# oresat-backplane-1u.net
KiCad netlist of a schematic drawn in EAGLE
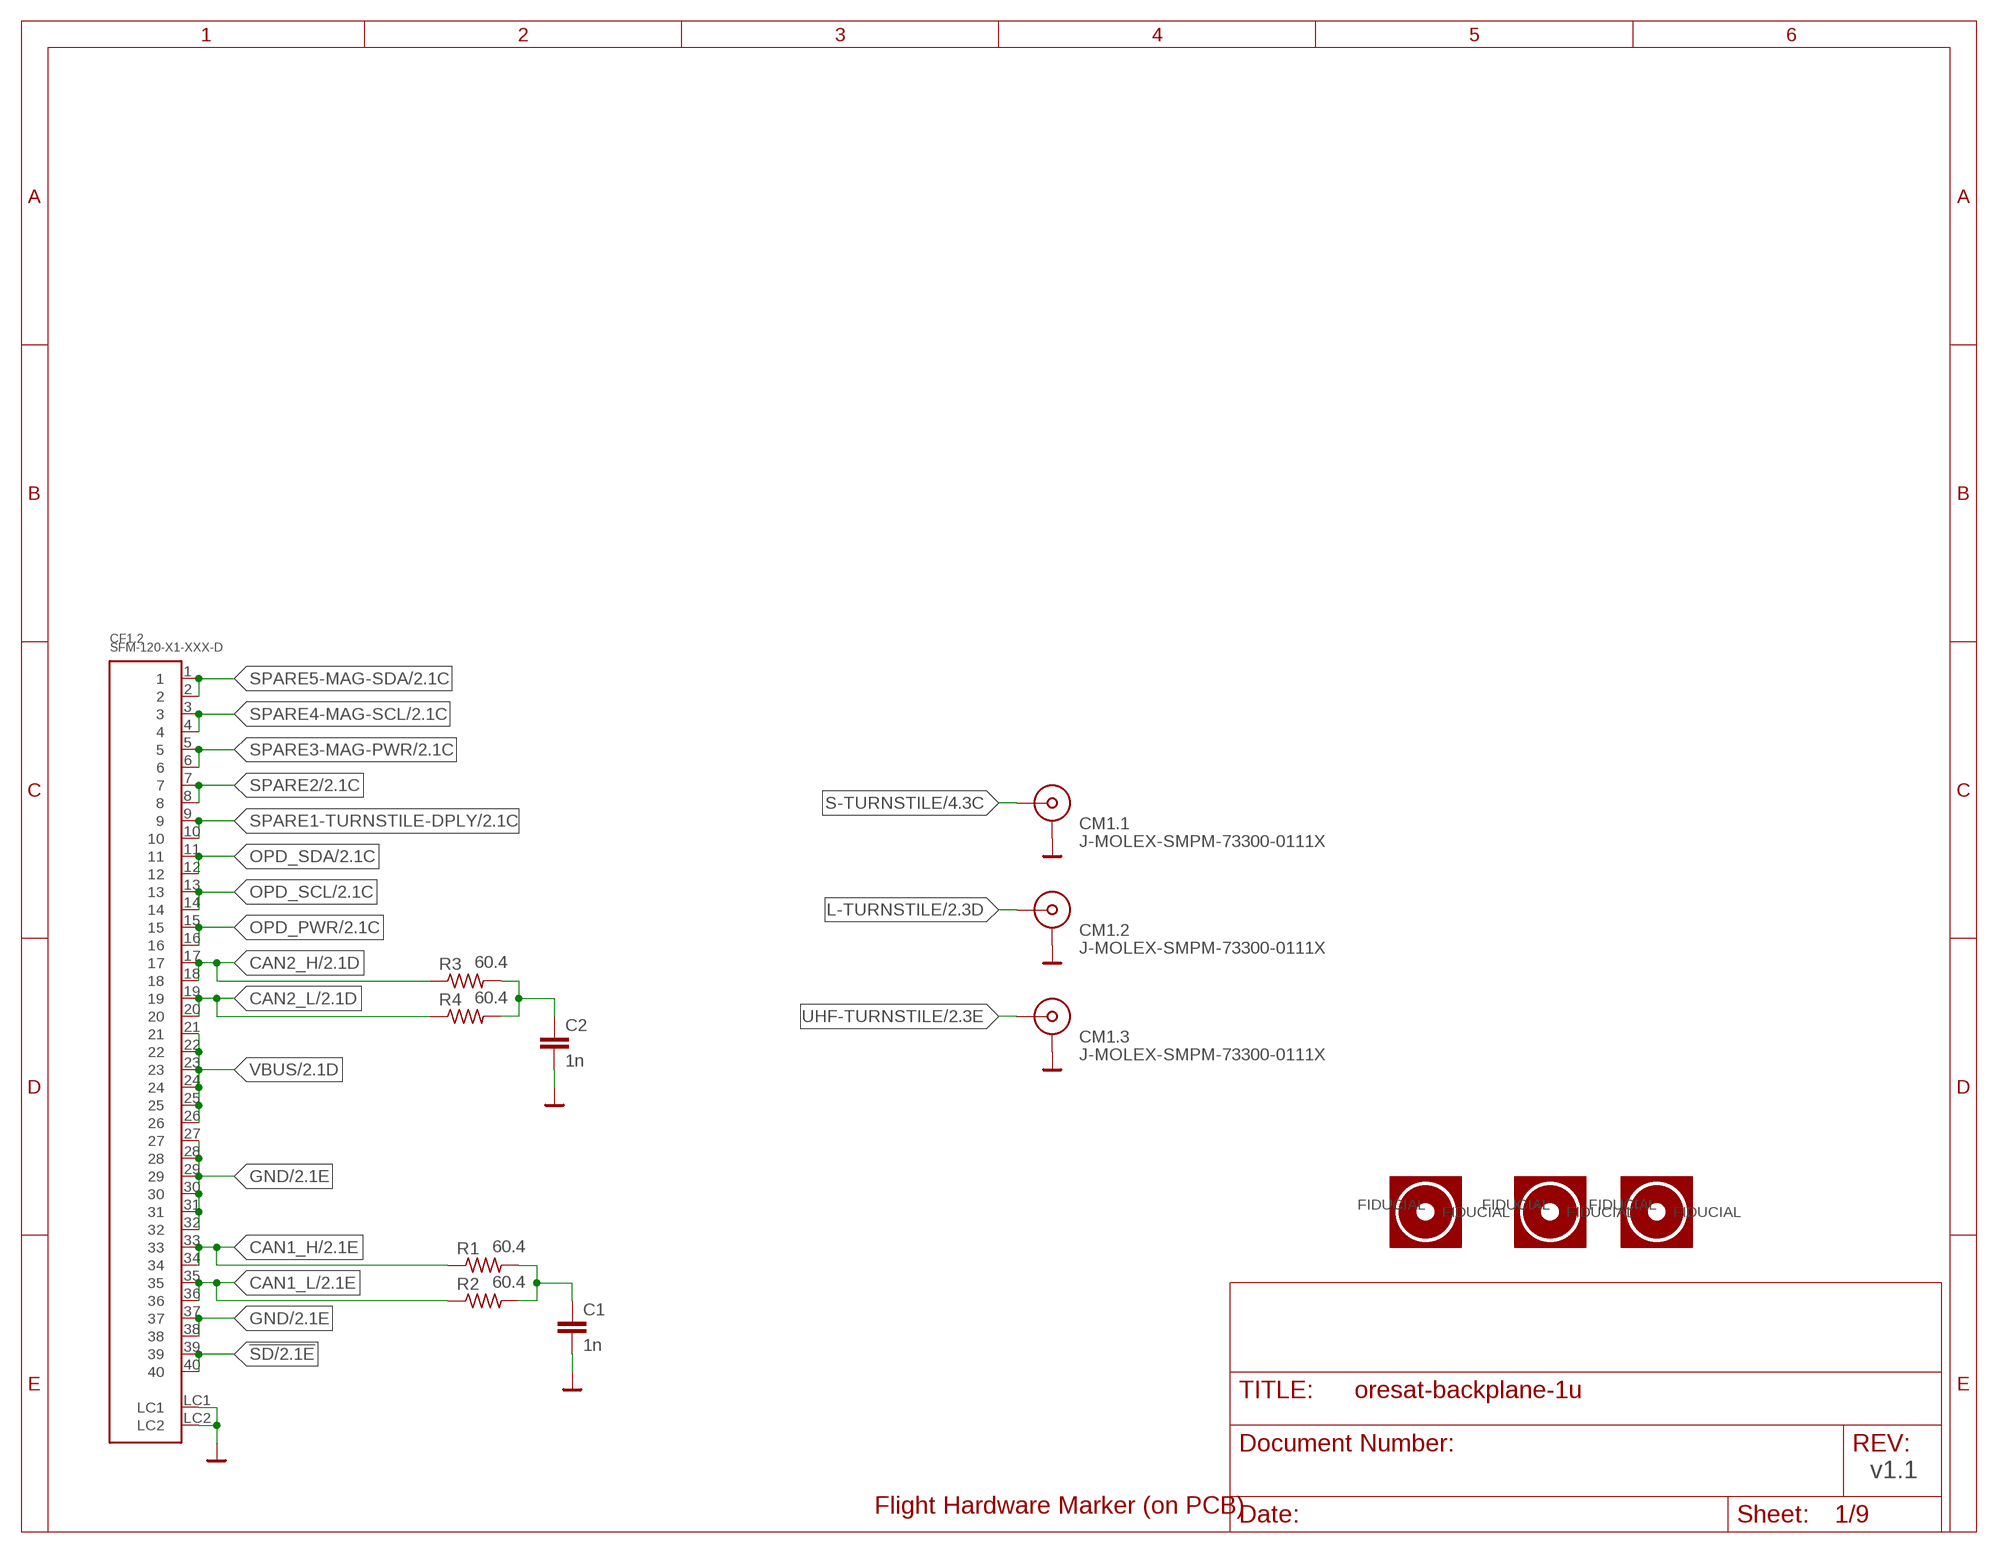
[diagram p0: schematic, sheet 1]
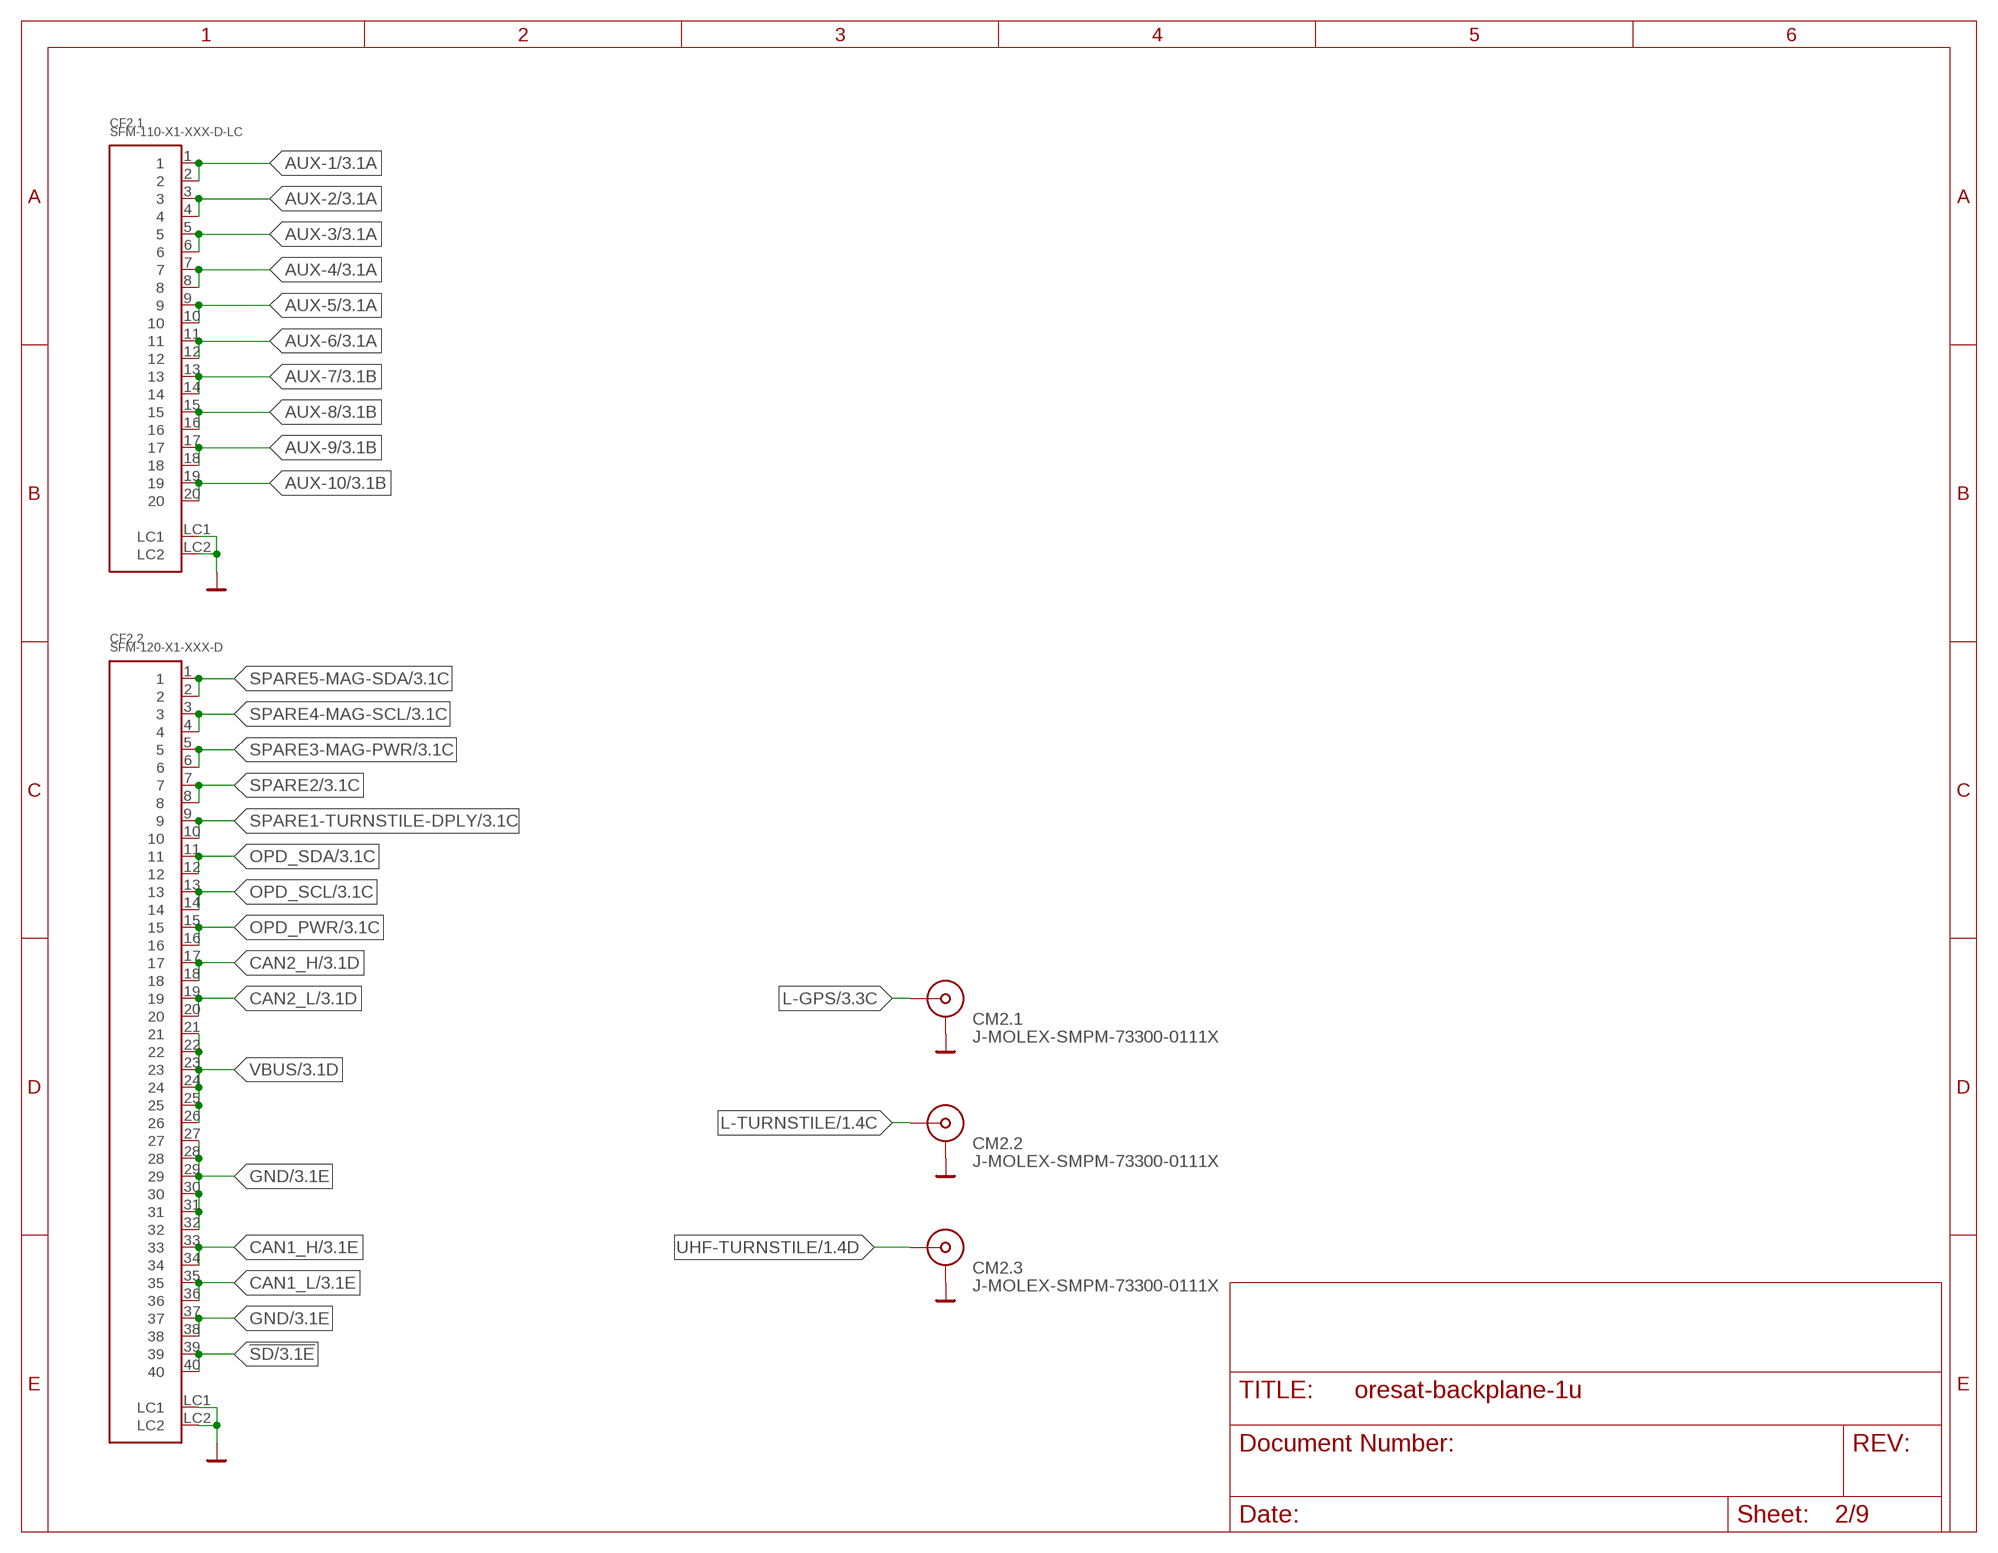
[diagram p1: schematic, sheet 2]
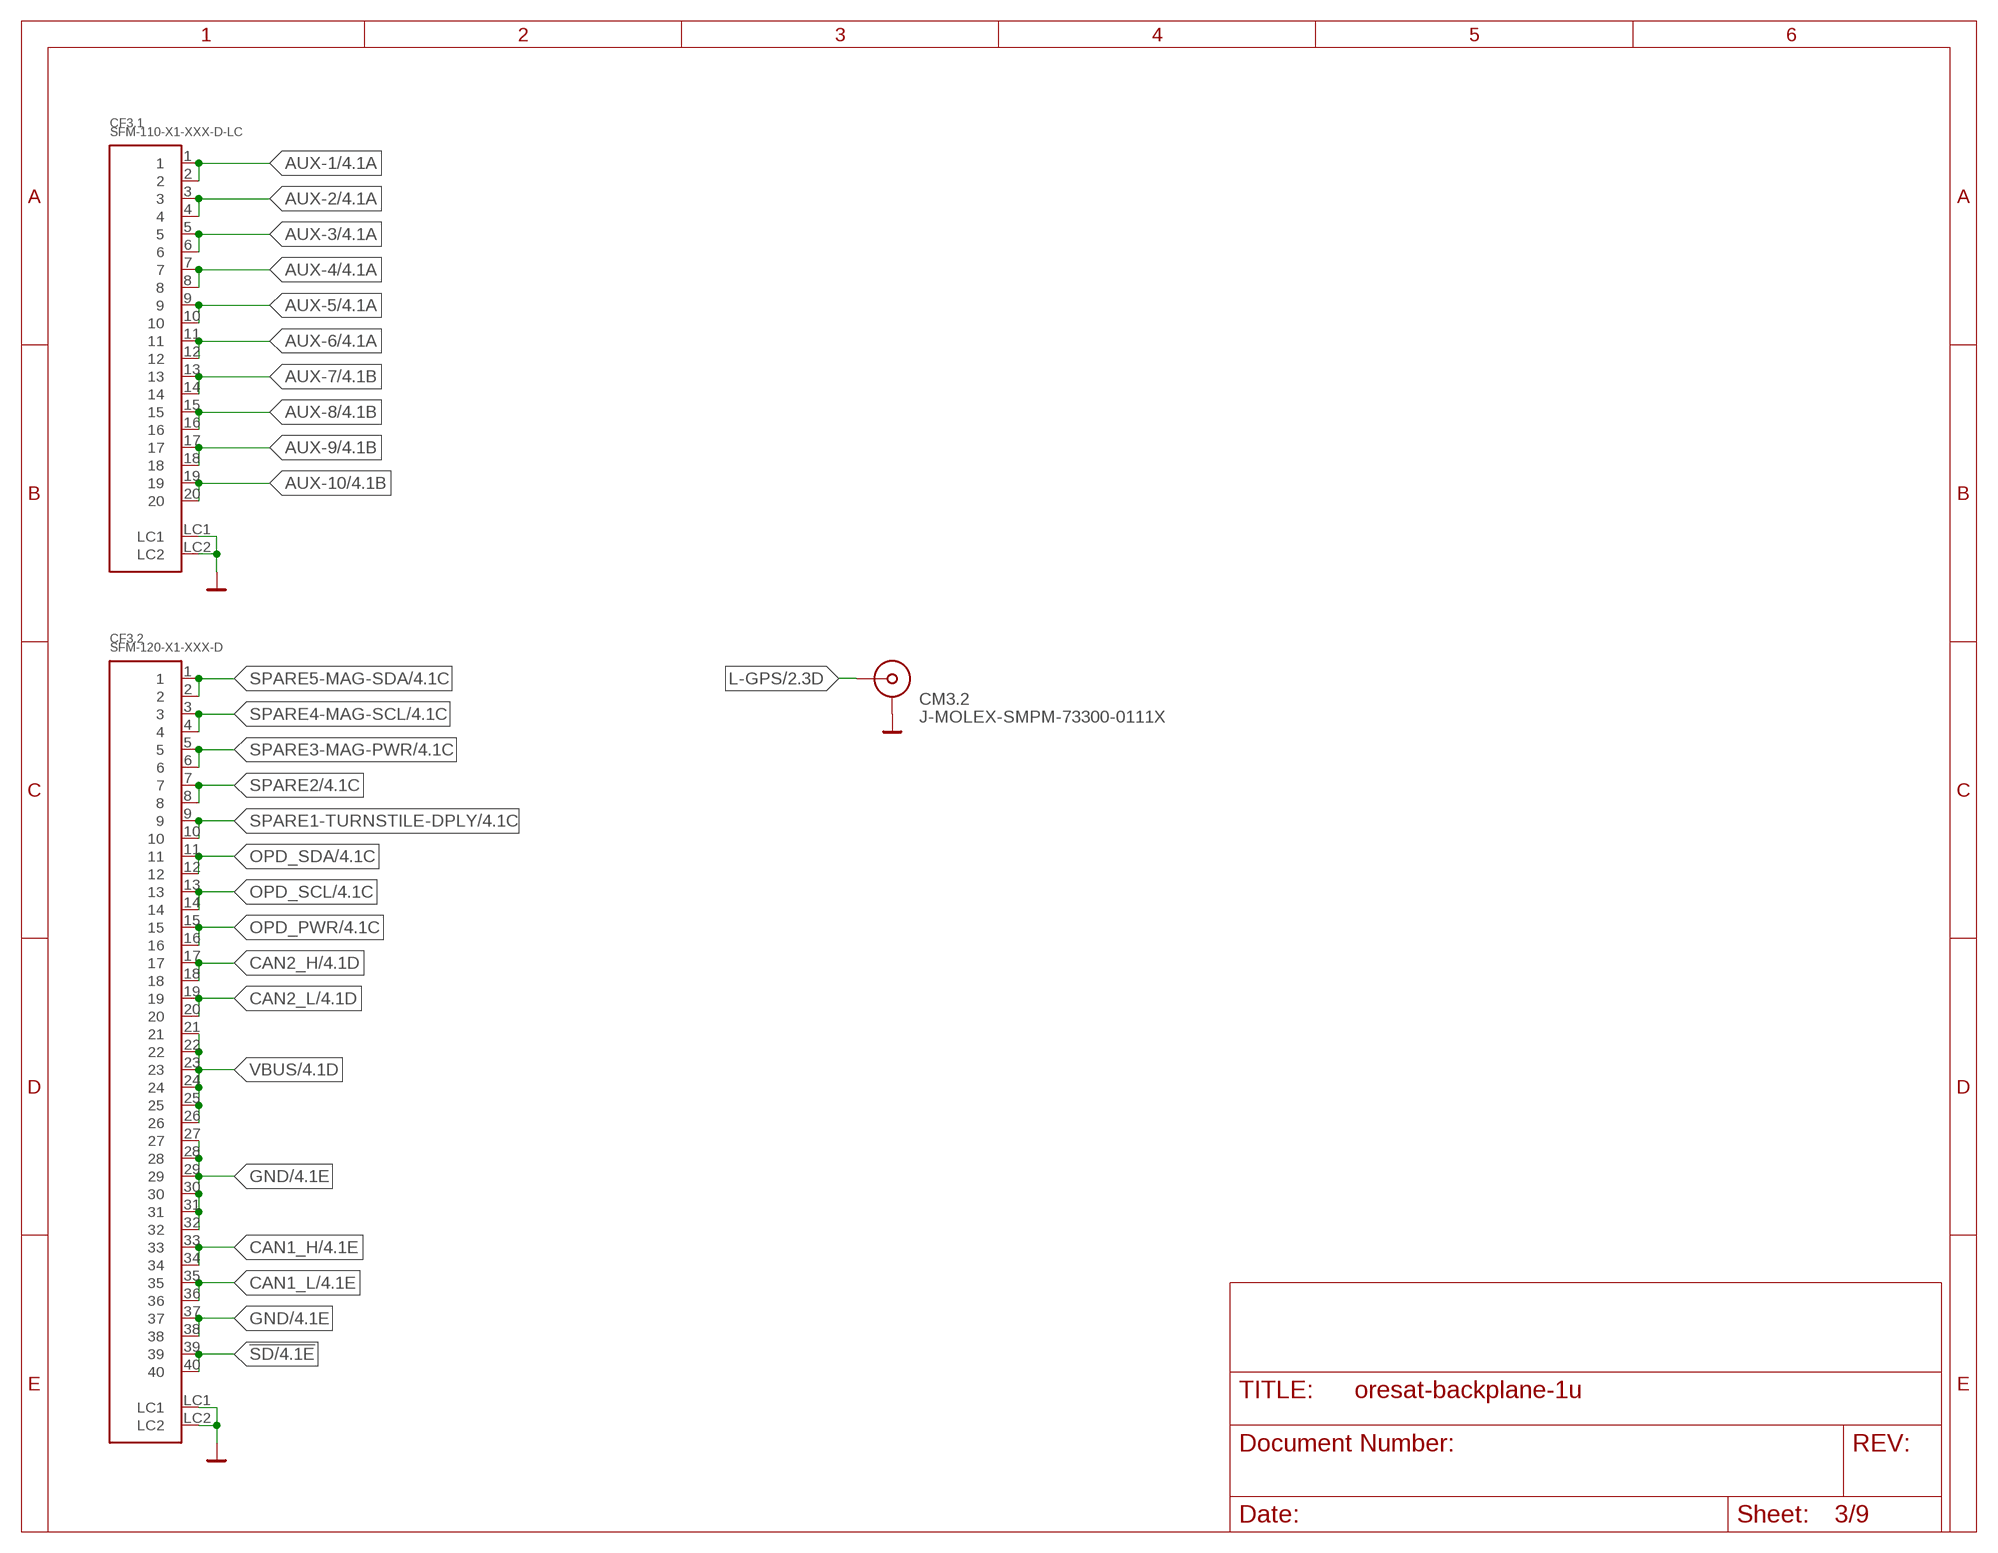
[diagram p2: schematic, sheet 3]
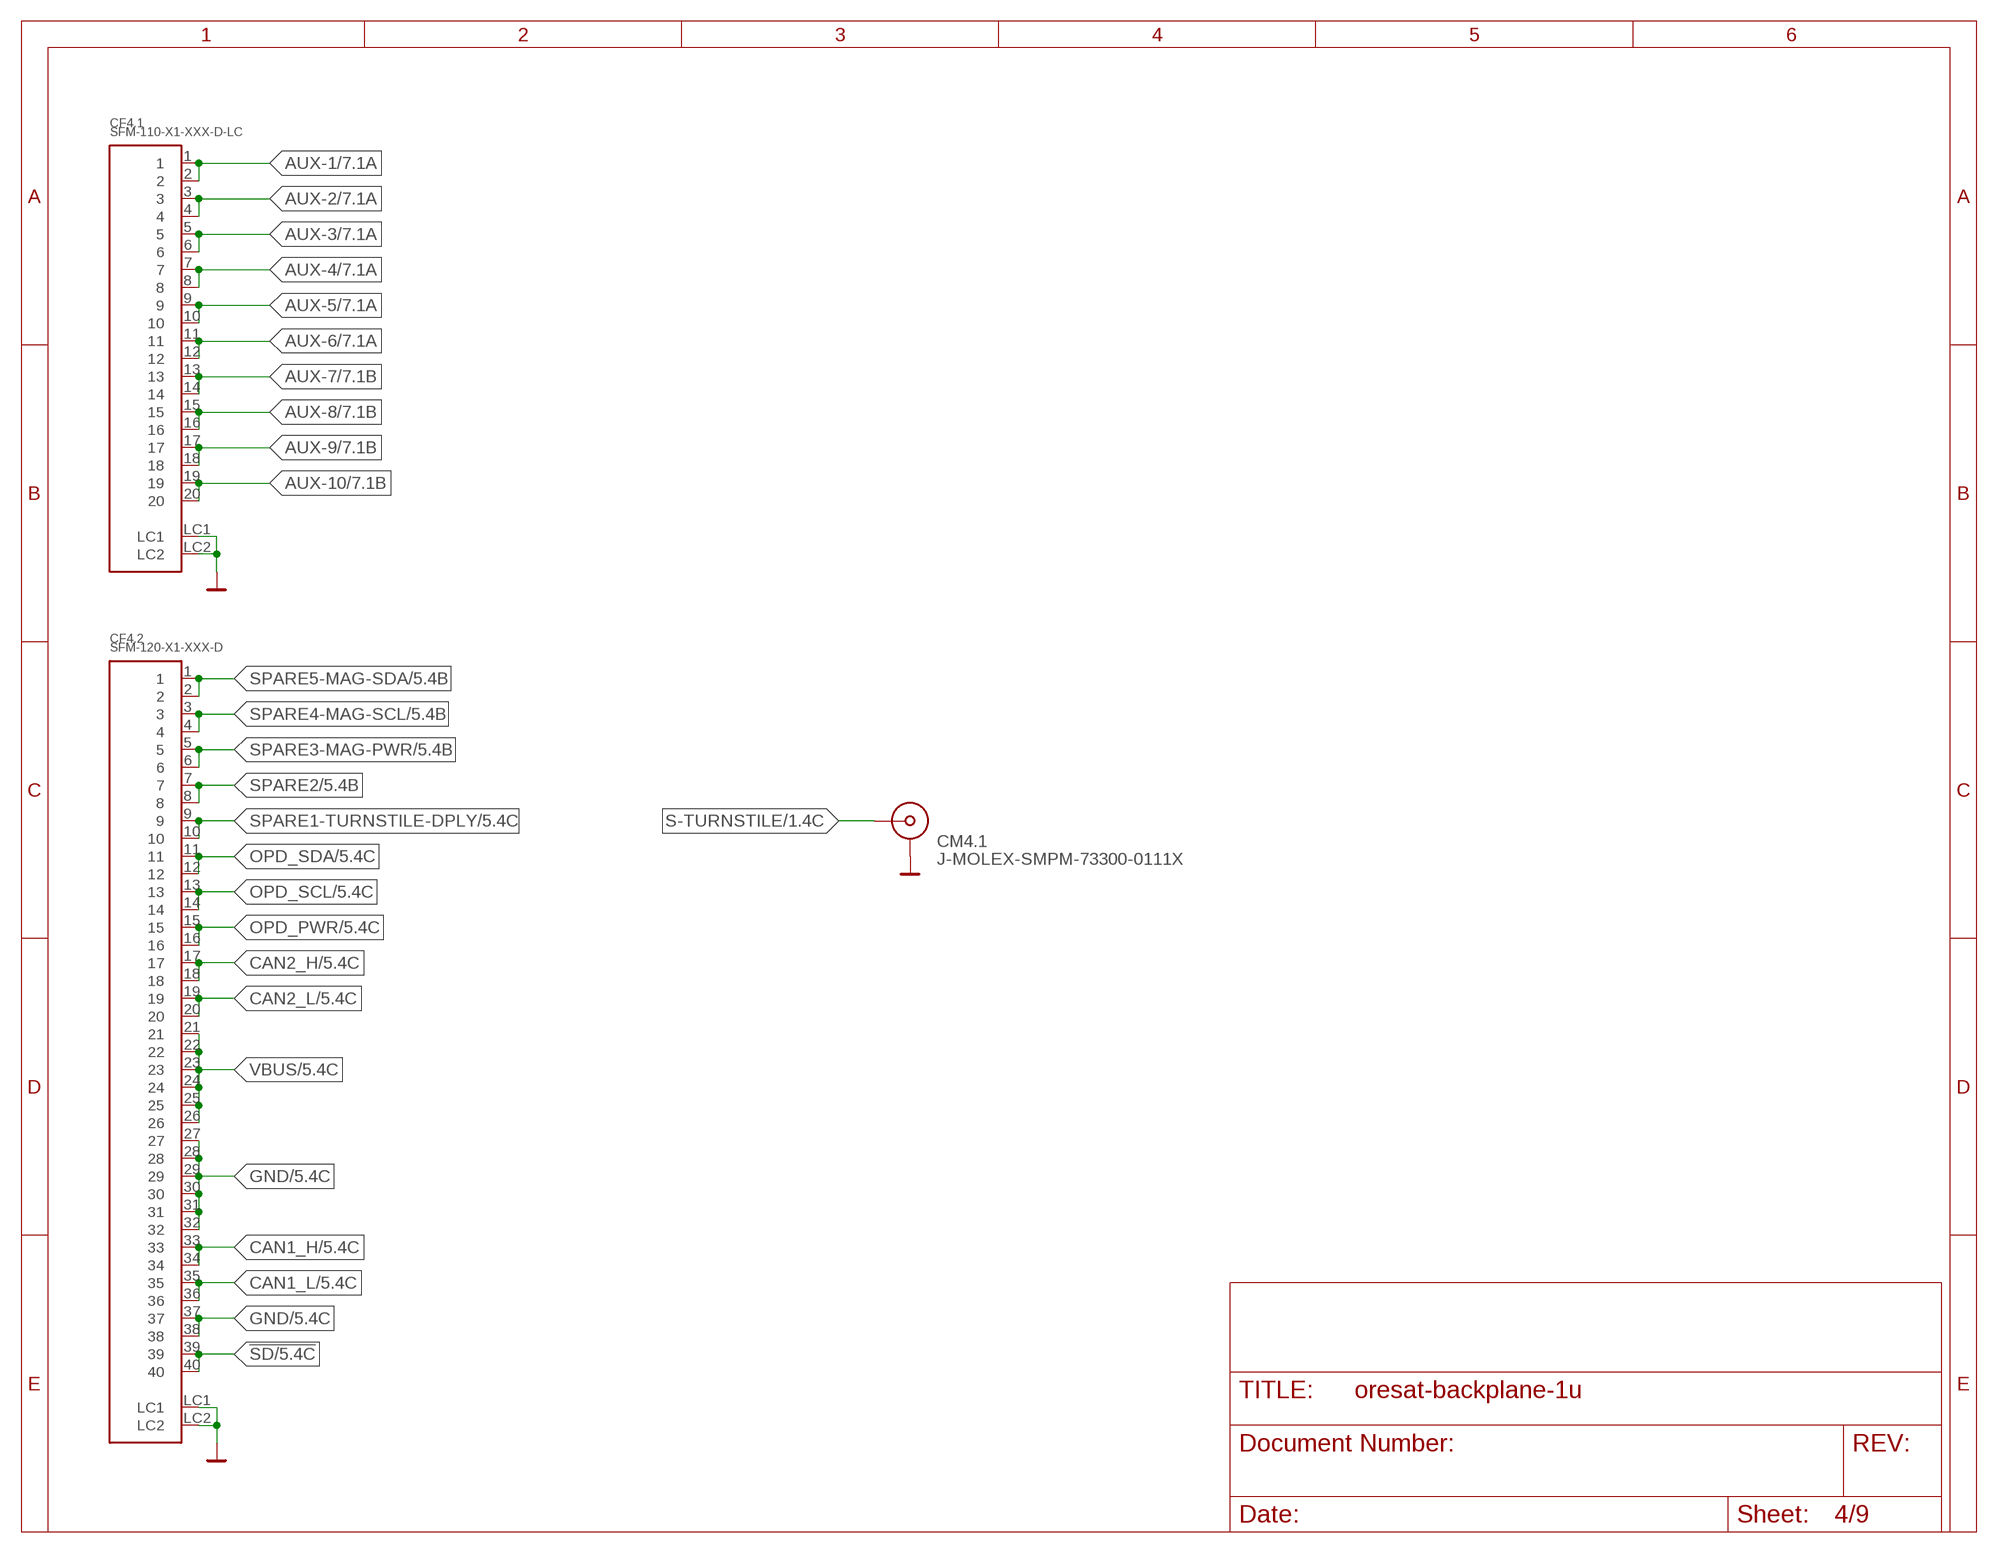
[diagram p3: schematic, sheet 4]
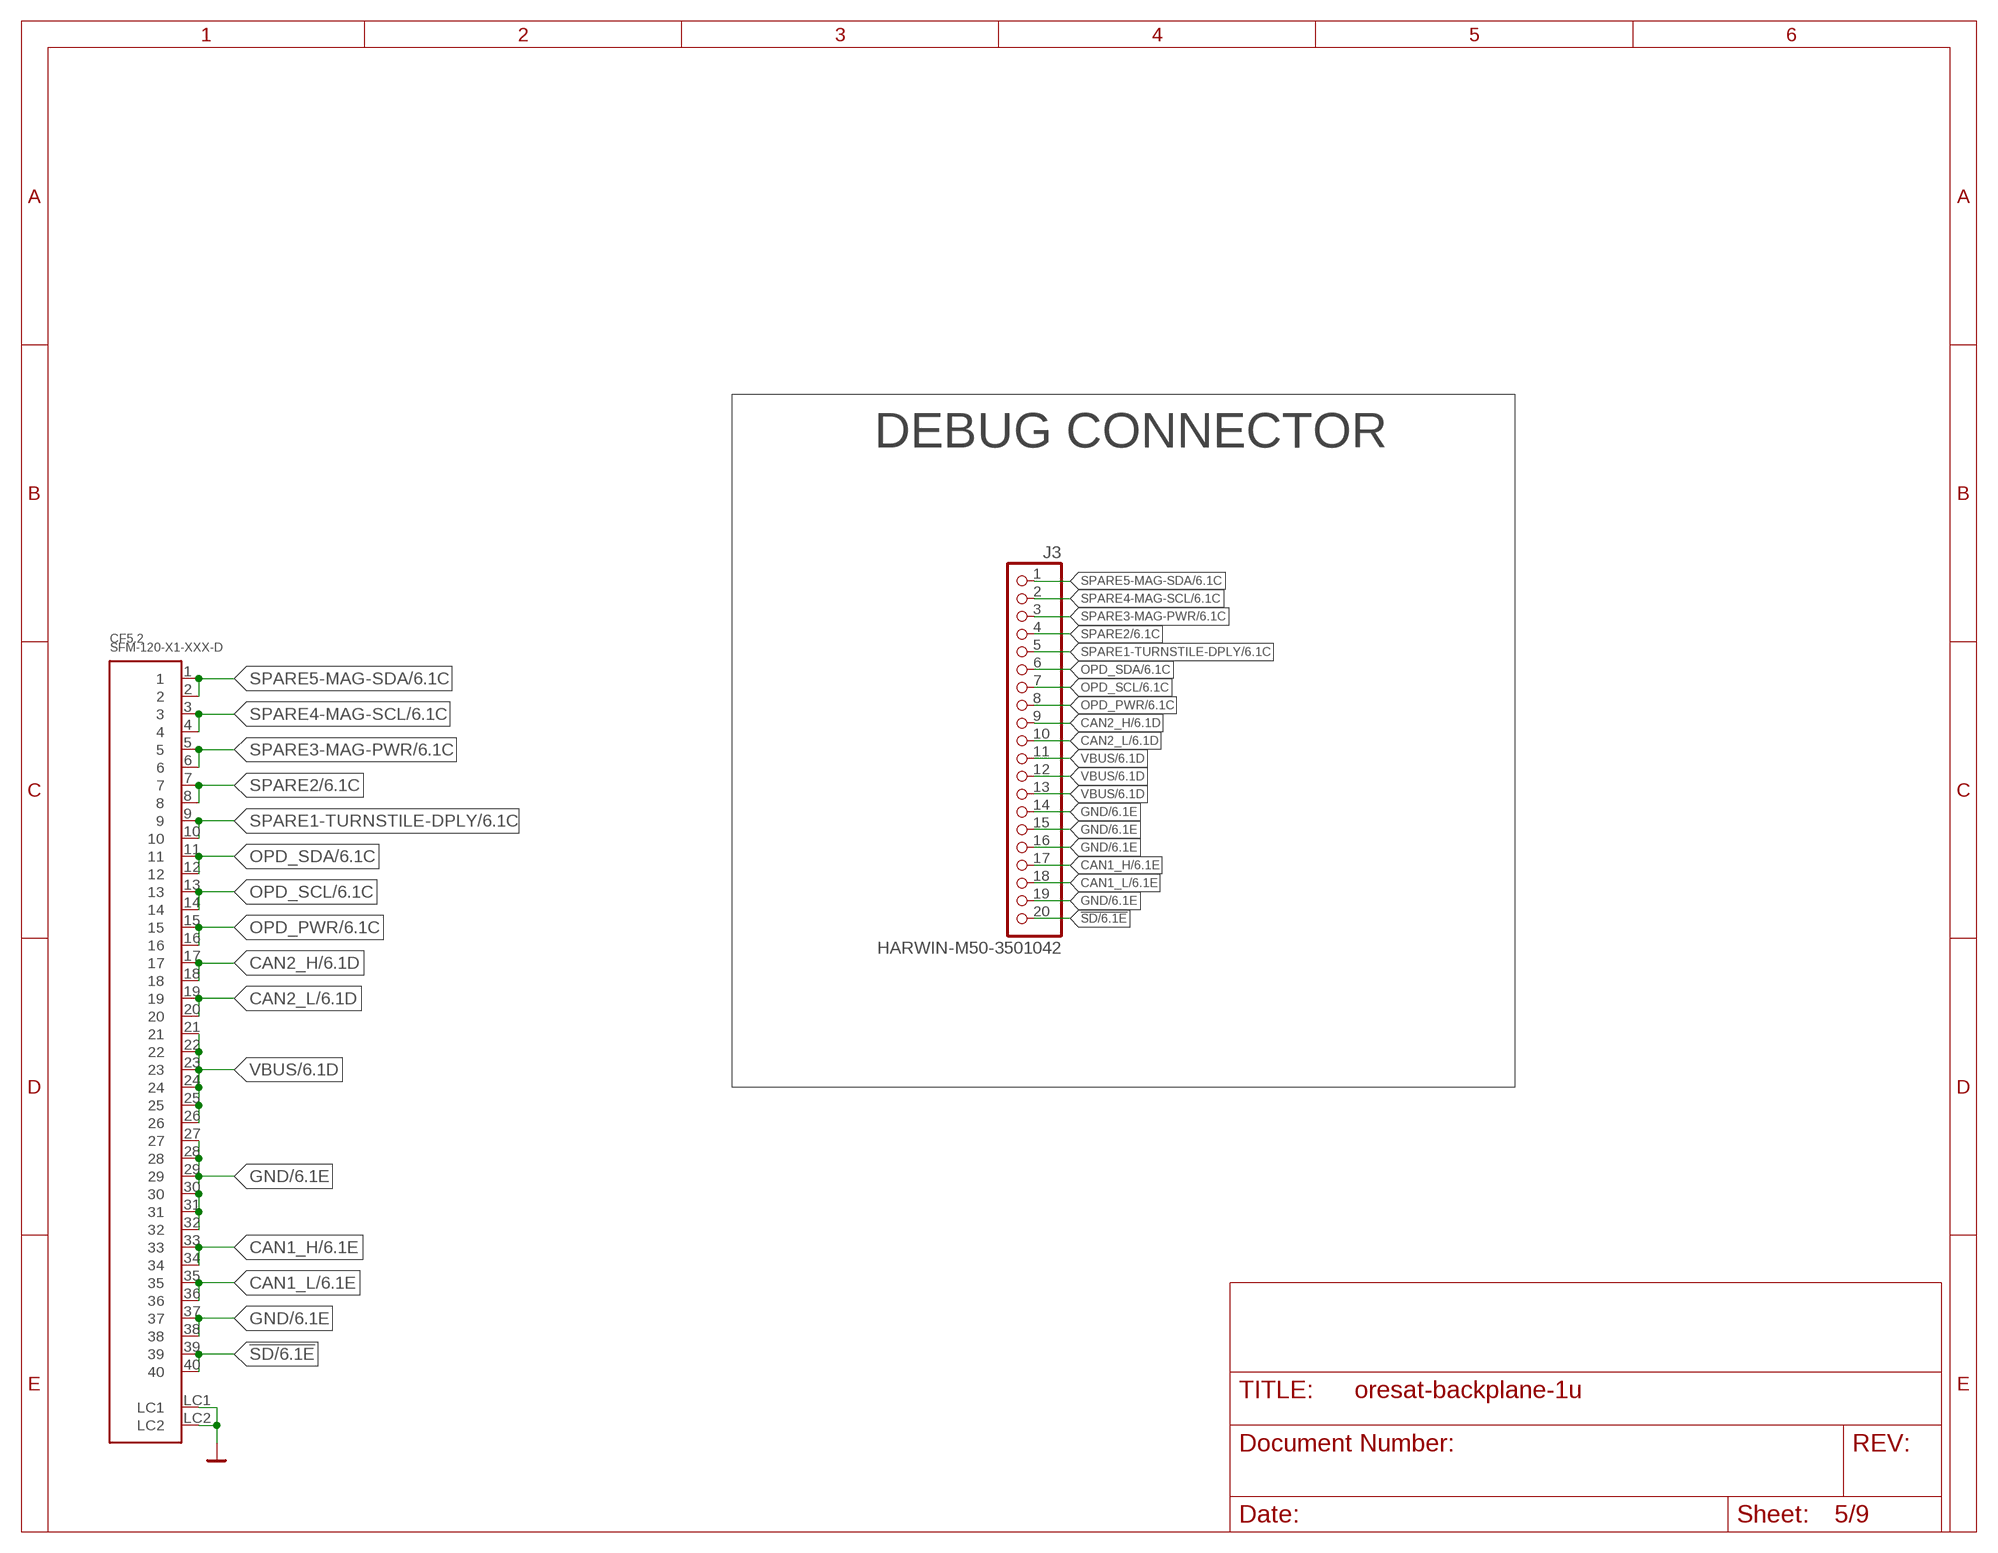
[diagram p4: schematic, sheet 5]
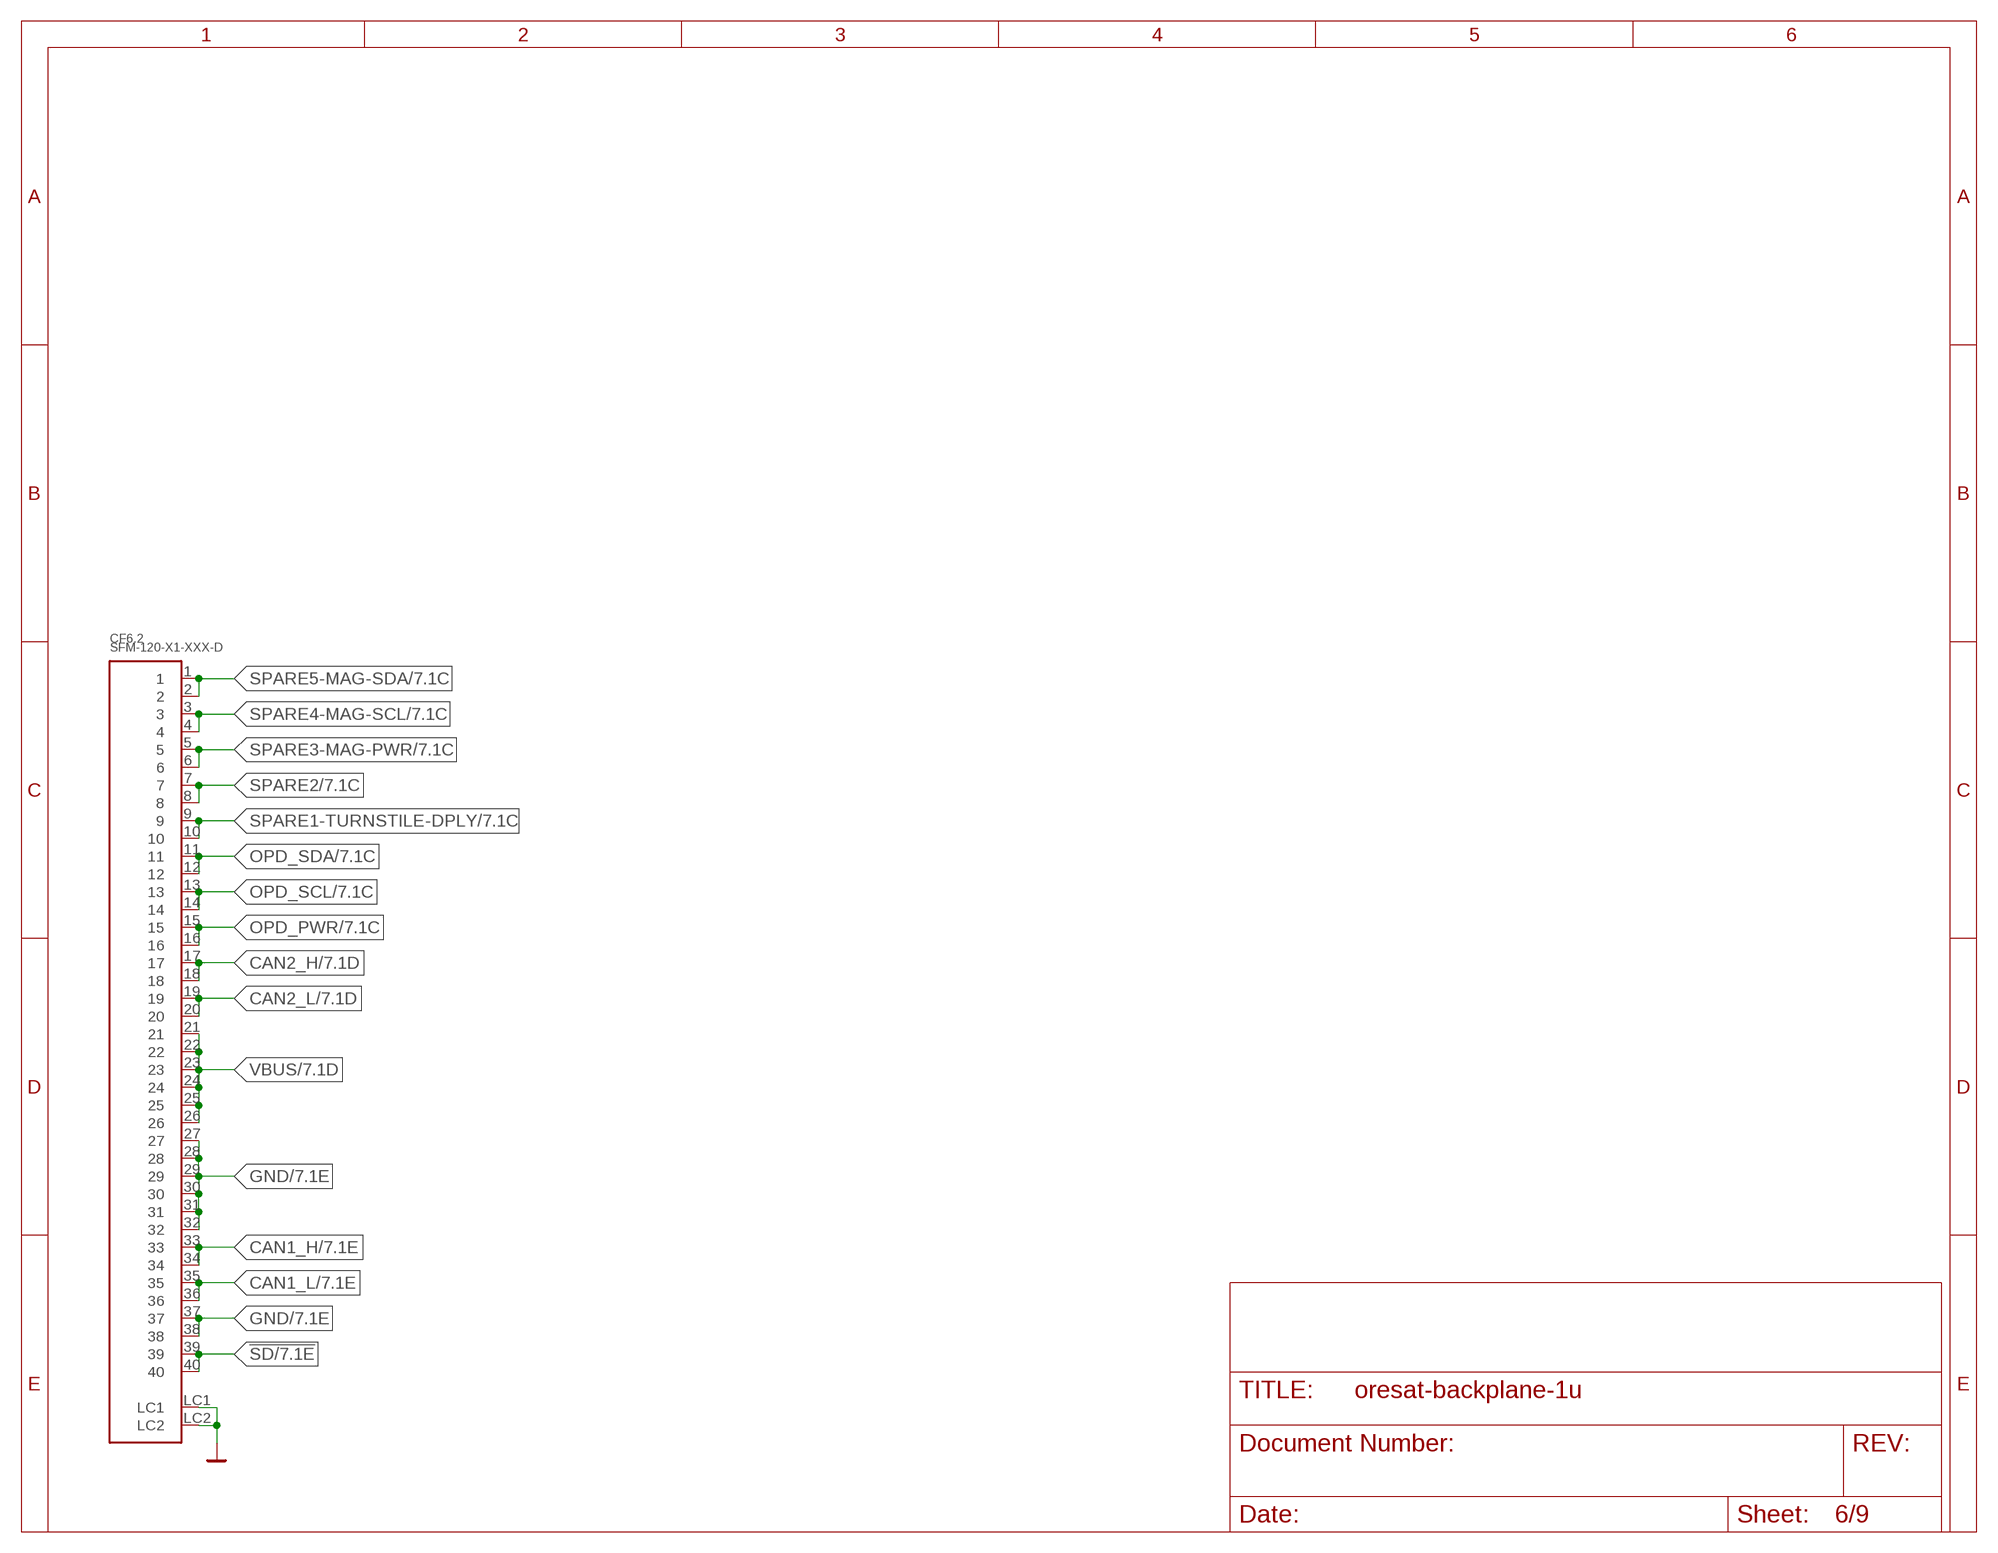
[diagram p5: schematic, sheet 6]
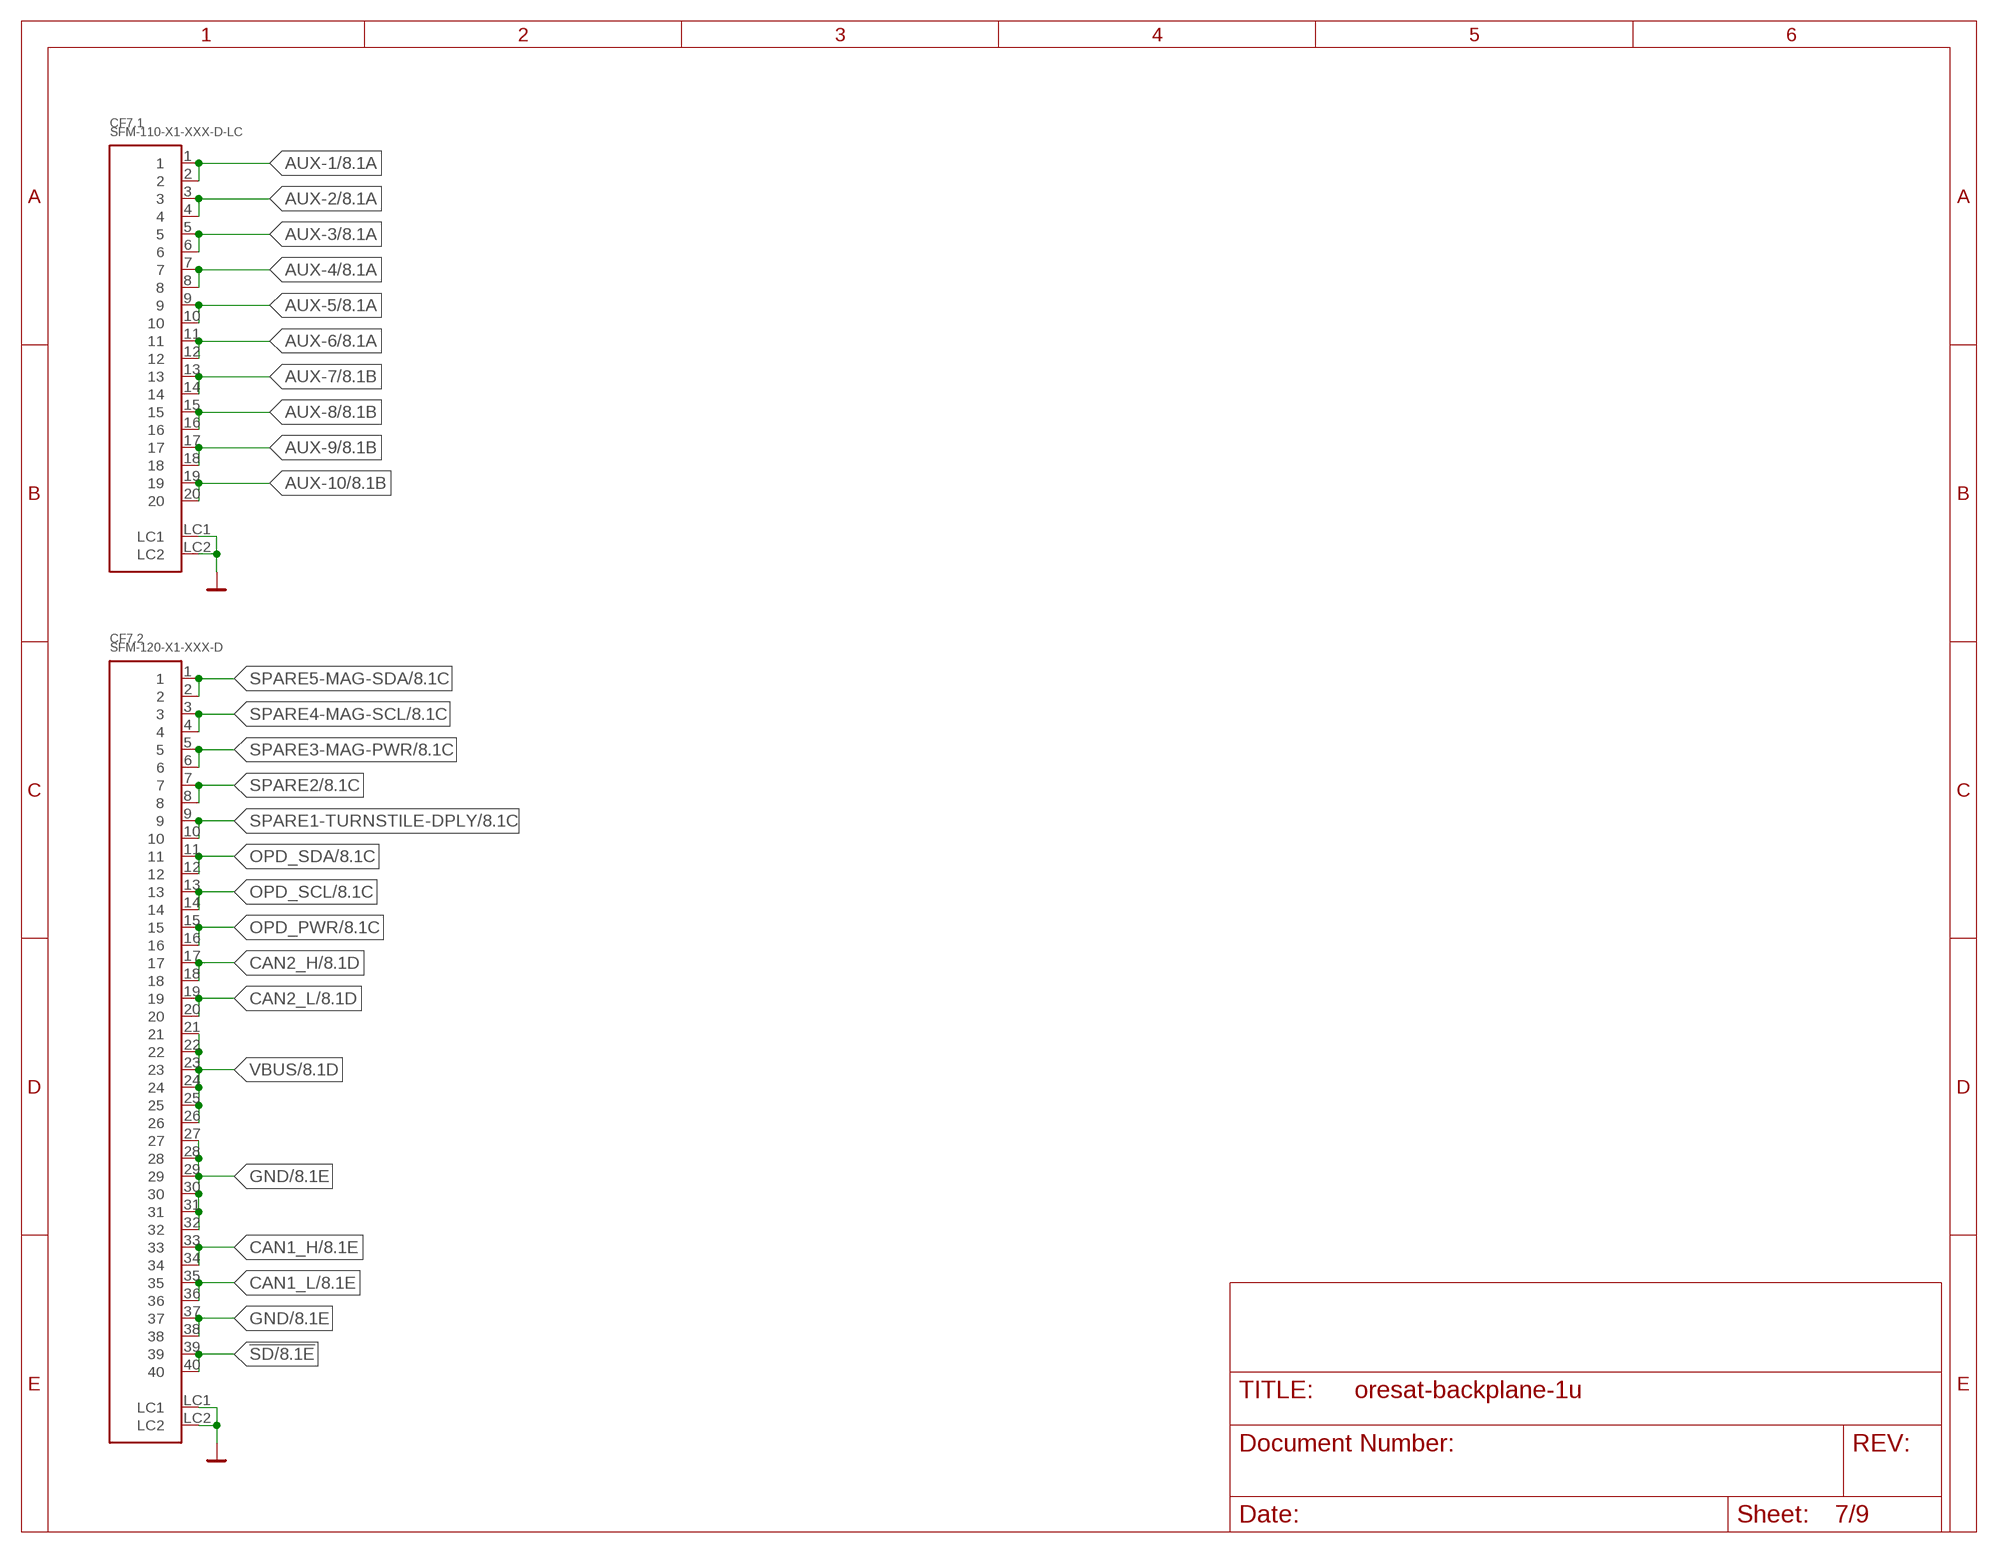
[diagram p6: schematic, sheet 7]
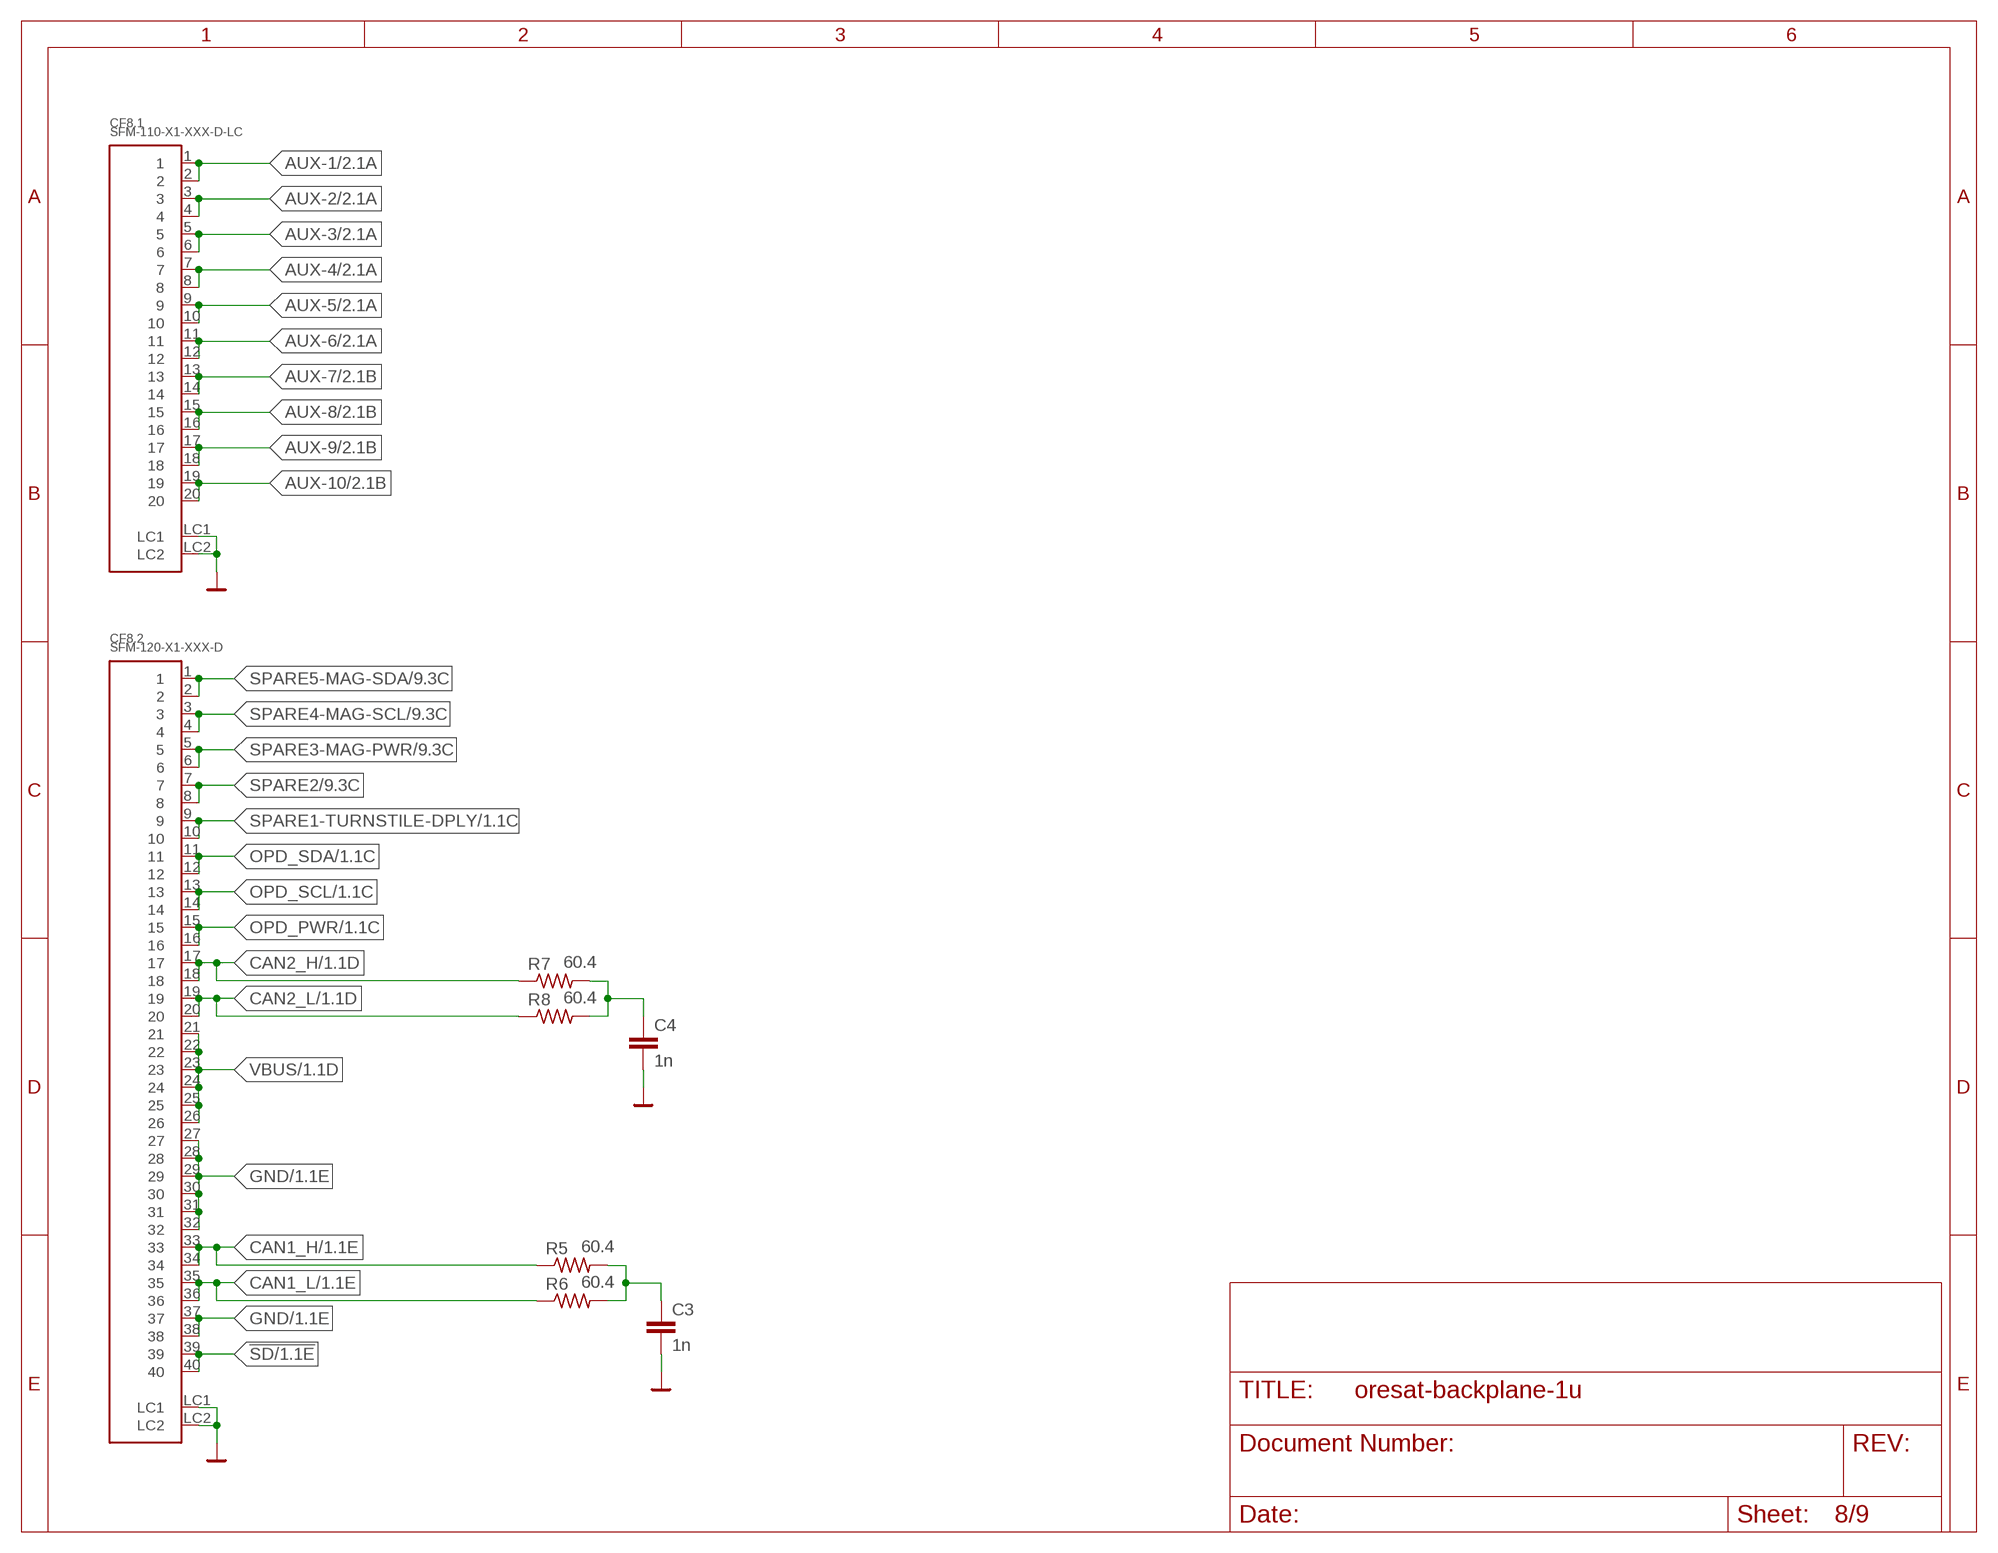
[diagram p7: schematic, sheet 8]
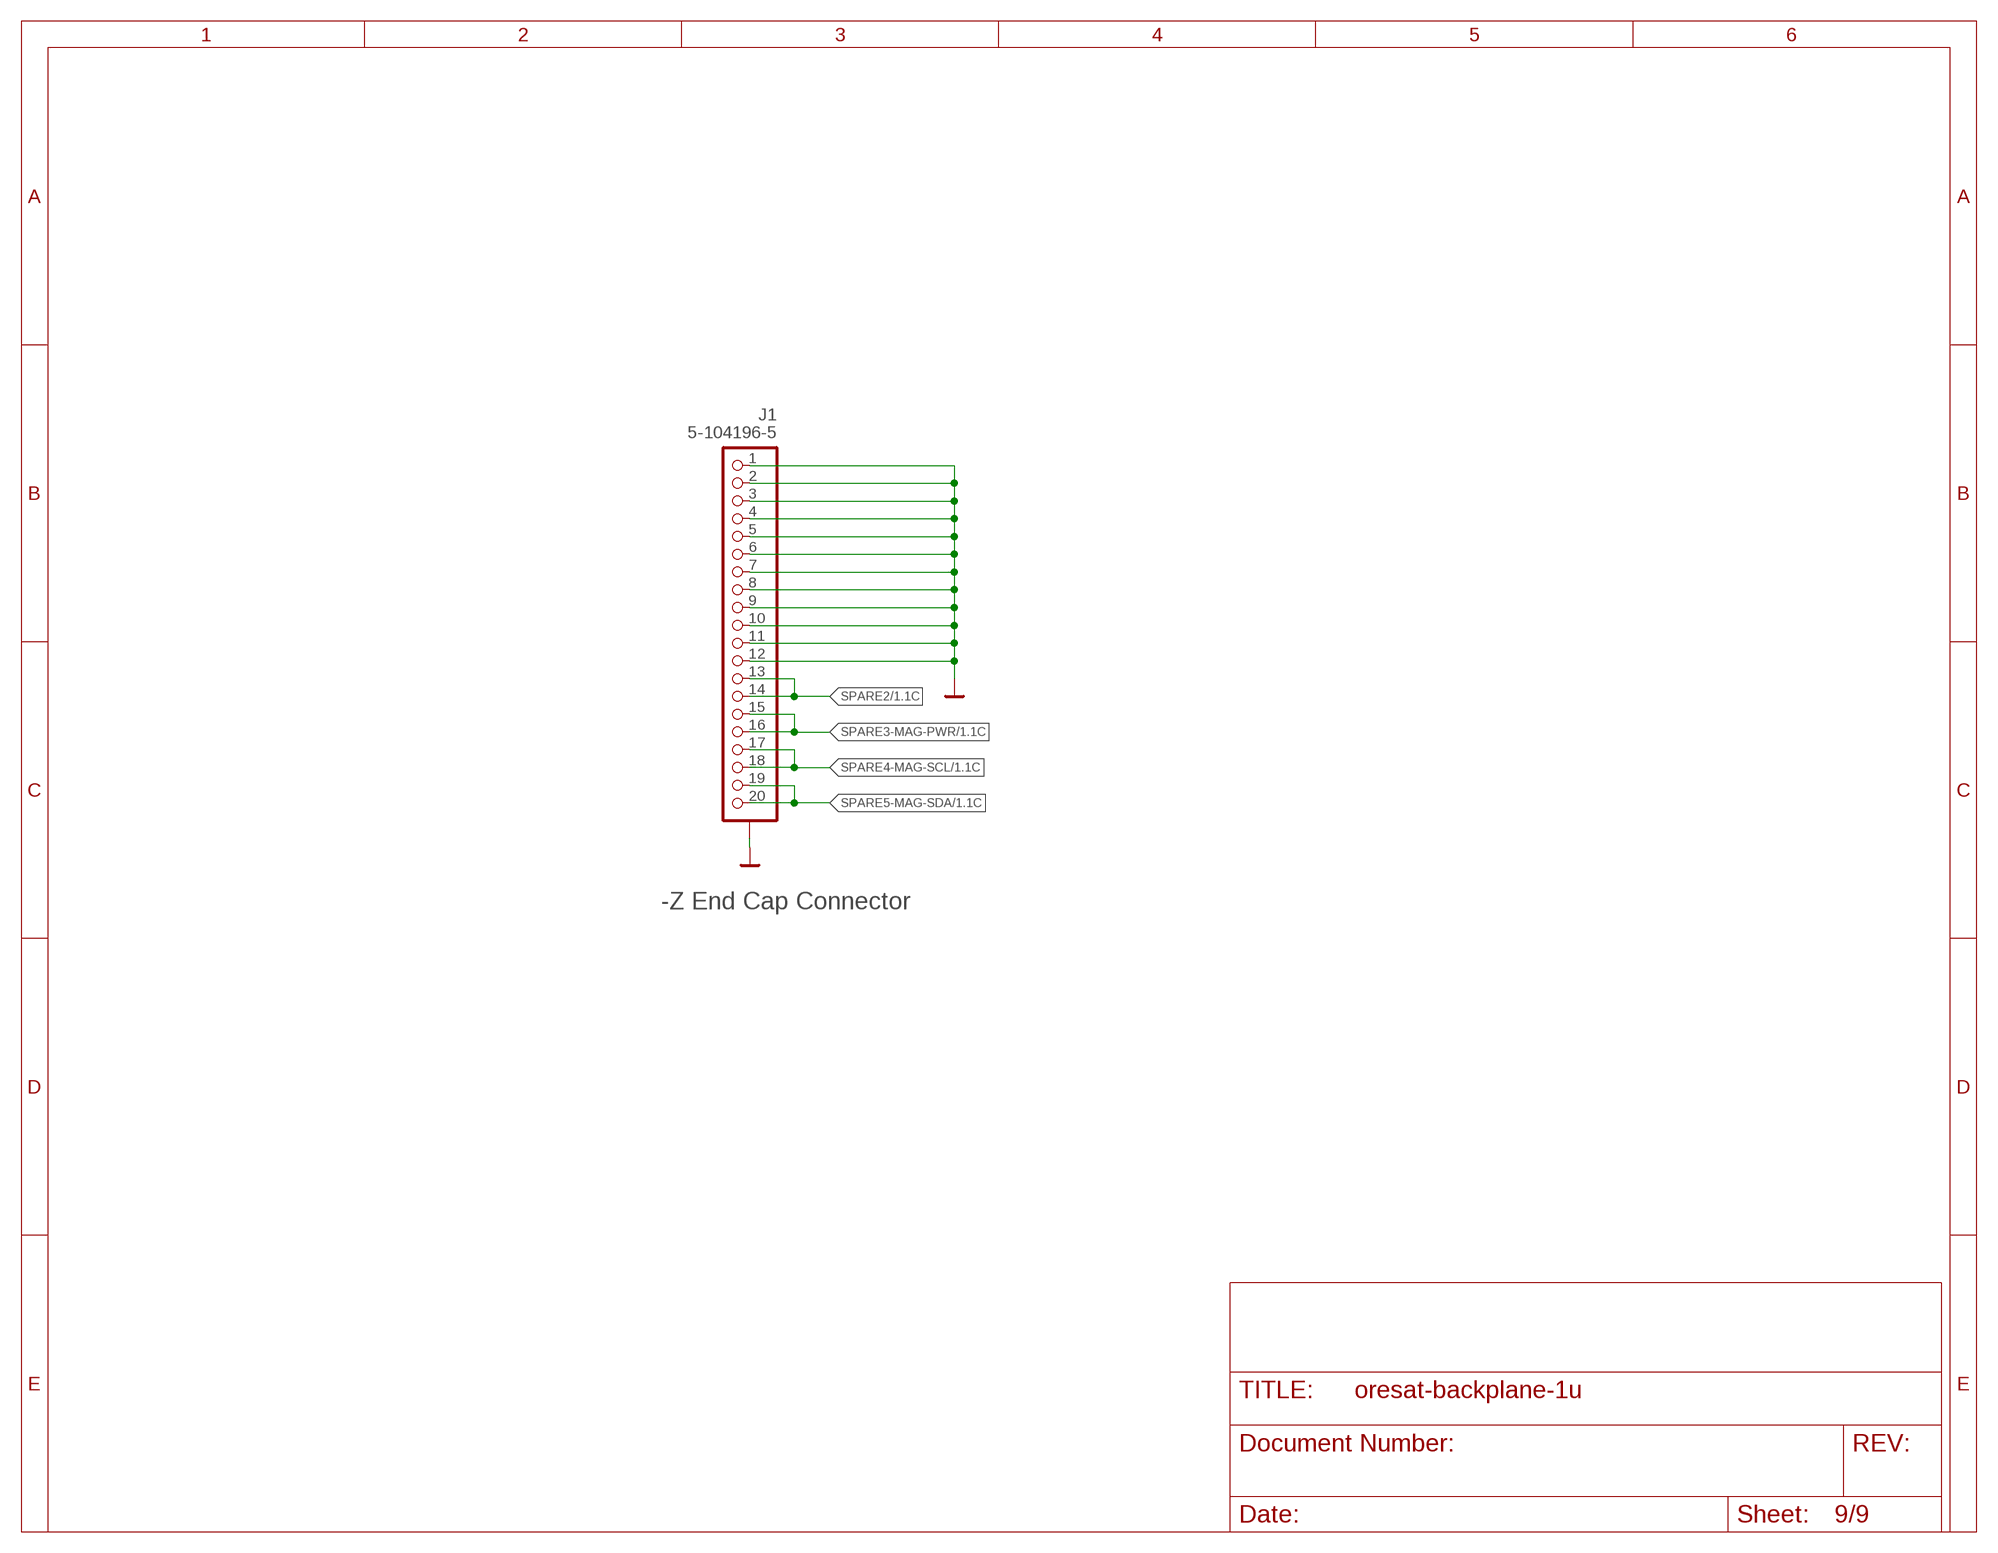
[diagram p8: schematic, sheet 9]

(export (version "E")
  (design (tool "Eeschema 10.0.6"))
  (components
    (comp (ref "CF5.2")
      (value "SFM-120-X1-XXX-D")
      (footprint "eagle-import:SFM-120-X1-XXX-D")
      (libsource (lib "eagle-import") (part "SFM-120-X1-XXX-D"))
    )
    (comp (ref "J3")
      (value "HARWIN-M50-3501042")
      (footprint "eagle-import:HARWIN-M50-3501042")
      (libsource (lib "eagle-import") (part "HARWIN-M50-3501042"))
    )
    (comp (ref "CF6.2")
      (value "SFM-120-X1-XXX-D")
      (footprint "eagle-import:SFM-120-X1-XXX-D")
      (libsource (lib "eagle-import") (part "SFM-120-X1-XXX-D"))
    )
    (comp (ref "CF4.1")
      (value "SFM-110-X1-XXX-D-LC")
      (footprint "eagle-import:SFM-110-X1-XXX-D-LC")
      (libsource (lib "eagle-import") (part "SFM-110-X1-XXX-D-LC"))
    )
    (comp (ref "CF4.2")
      (value "SFM-120-X1-XXX-D")
      (footprint "eagle-import:SFM-120-X1-XXX-D")
      (libsource (lib "eagle-import") (part "SFM-120-X1-XXX-D"))
    )
    (comp (ref "CM4.1")
      (value "J-MOLEX-SMPM-73300-0111X")
      (footprint "eagle-import:J-MOLEX-SMPM-73300-0111X")
      (libsource (lib "eagle-import") (part "J-MOLEX-SMPM-73300-0111X"))
    )
    (comp (ref "J1")
      (value "5-104196-5")
      (footprint "eagle-import:5-104196-5")
      (libsource (lib "eagle-import") (part "5-104196-5"))
    )
    (comp (ref "C3")
      (value "1n")
      (footprint "eagle-import:.0603-C-NOSILK")
      (libsource (lib "eagle-import") (part "C-EU0603-C-NOSILK"))
    )
    (comp (ref "C4")
      (value "1n")
      (footprint "eagle-import:.0603-C-NOSILK")
      (libsource (lib "eagle-import") (part "C-EU0603-C-NOSILK"))
    )
    (comp (ref "CF8.1")
      (value "SFM-110-X1-XXX-D-LC")
      (footprint "eagle-import:SFM-110-X1-XXX-D-LC")
      (libsource (lib "eagle-import") (part "SFM-110-X1-XXX-D-LC"))
    )
    (comp (ref "CF8.2")
      (value "SFM-120-X1-XXX-D")
      (footprint "eagle-import:SFM-120-X1-XXX-D")
      (libsource (lib "eagle-import") (part "SFM-120-X1-XXX-D"))
    )
    (comp (ref "R5")
      (value "60.4")
      (footprint "eagle-import:1206-C")
      (libsource (lib "eagle-import") (part "R-US_1206-C"))
    )
    (comp (ref "R6")
      (value "60.4")
      (footprint "eagle-import:1206-C")
      (libsource (lib "eagle-import") (part "R-US_1206-C"))
    )
    (comp (ref "R7")
      (value "60.4")
      (footprint "eagle-import:1206-C")
      (libsource (lib "eagle-import") (part "R-US_1206-C"))
    )
    (comp (ref "R8")
      (value "60.4")
      (footprint "eagle-import:1206-C")
      (libsource (lib "eagle-import") (part "R-US_1206-C"))
    )
    (comp (ref "CF7.1")
      (value "SFM-110-X1-XXX-D-LC")
      (footprint "eagle-import:SFM-110-X1-XXX-D-LC")
      (libsource (lib "eagle-import") (part "SFM-110-X1-XXX-D-LC"))
    )
    (comp (ref "CF7.2")
      (value "SFM-120-X1-XXX-D")
      (footprint "eagle-import:SFM-120-X1-XXX-D")
      (libsource (lib "eagle-import") (part "SFM-120-X1-XXX-D"))
    )
    (comp (ref "CF2.1")
      (value "SFM-110-X1-XXX-D-LC")
      (footprint "eagle-import:SFM-110-X1-XXX-D-LC")
      (libsource (lib "eagle-import") (part "SFM-110-X1-XXX-D-LC"))
    )
    (comp (ref "CF2.2")
      (value "SFM-120-X1-XXX-D")
      (footprint "eagle-import:SFM-120-X1-XXX-D")
      (libsource (lib "eagle-import") (part "SFM-120-X1-XXX-D"))
    )
    (comp (ref "CM2.1")
      (value "J-MOLEX-SMPM-73300-0111X")
      (footprint "eagle-import:J-MOLEX-SMPM-73300-0111X")
      (libsource (lib "eagle-import") (part "J-MOLEX-SMPM-73300-0111X"))
    )
    (comp (ref "CM2.2")
      (value "J-MOLEX-SMPM-73300-0111X")
      (footprint "eagle-import:J-MOLEX-SMPM-73300-0111X")
      (libsource (lib "eagle-import") (part "J-MOLEX-SMPM-73300-0111X"))
    )
    (comp (ref "CM2.3")
      (value "J-MOLEX-SMPM-73300-0111X")
      (footprint "eagle-import:J-MOLEX-SMPM-73300-0111X")
      (libsource (lib "eagle-import") (part "J-MOLEX-SMPM-73300-0111X"))
    )
    (comp (ref "C1")
      (value "1n")
      (footprint "eagle-import:.0603-C-NOSILK")
      (libsource (lib "eagle-import") (part "C-EU0603-C-NOSILK"))
    )
    (comp (ref "C2")
      (value "1n")
      (footprint "eagle-import:.0603-C-NOSILK")
      (libsource (lib "eagle-import") (part "C-EU0603-C-NOSILK"))
    )
    (comp (ref "CF1.2")
      (value "SFM-120-X1-XXX-D")
      (footprint "eagle-import:SFM-120-X1-XXX-D")
      (libsource (lib "eagle-import") (part "SFM-120-X1-XXX-D"))
    )
    (comp (ref "CM1.1")
      (value "J-MOLEX-SMPM-73300-0111X")
      (footprint "eagle-import:J-MOLEX-SMPM-73300-0111X")
      (libsource (lib "eagle-import") (part "J-MOLEX-SMPM-73300-0111X"))
    )
    (comp (ref "CM1.2")
      (value "J-MOLEX-SMPM-73300-0111X")
      (footprint "eagle-import:J-MOLEX-SMPM-73300-0111X")
      (libsource (lib "eagle-import") (part "J-MOLEX-SMPM-73300-0111X"))
    )
    (comp (ref "CM1.3")
      (value "J-MOLEX-SMPM-73300-0111X")
      (footprint "eagle-import:J-MOLEX-SMPM-73300-0111X")
      (libsource (lib "eagle-import") (part "J-MOLEX-SMPM-73300-0111X"))
    )
    (comp (ref "FIDUCIAL1")
      (value "FIDUCIAL-1.0X2.0")
      (footprint "eagle-import:FIDUCIAL-1.0X2.0")
      (libsource (lib "eagle-import") (part "FIDUCIAL-1.0X2.0"))
    )
    (comp (ref "FIDUCIAL2")
      (value "FIDUCIAL-1.0X2.0")
      (footprint "eagle-import:FIDUCIAL-1.0X2.0")
      (libsource (lib "eagle-import") (part "FIDUCIAL-1.0X2.0"))
    )
    (comp (ref "FIDUCIAL3")
      (value "FIDUCIAL-1.0X2.0")
      (footprint "eagle-import:FIDUCIAL-1.0X2.0")
      (libsource (lib "eagle-import") (part "FIDUCIAL-1.0X2.0"))
    )
    (comp (ref "R1")
      (value "60.4")
      (footprint "eagle-import:1206-C")
      (libsource (lib "eagle-import") (part "R-US_1206-C"))
    )
    (comp (ref "R2")
      (value "60.4")
      (footprint "eagle-import:1206-C")
      (libsource (lib "eagle-import") (part "R-US_1206-C"))
    )
    (comp (ref "R3")
      (value "60.4")
      (footprint "eagle-import:1206-C")
      (libsource (lib "eagle-import") (part "R-US_1206-C"))
    )
    (comp (ref "R4")
      (value "60.4")
      (footprint "eagle-import:1206-C")
      (libsource (lib "eagle-import") (part "R-US_1206-C"))
    )
    (comp (ref "U$1")
      (value "FLIGHMARKERNEW")
      (footprint "eagle-import:FLIGHTMARKER_NEW_BOARDS")
      (libsource (lib "eagle-import") (part "FLIGHMARKERNEW"))
    )
    (comp (ref "CF3.1")
      (value "SFM-110-X1-XXX-D-LC")
      (footprint "eagle-import:SFM-110-X1-XXX-D-LC")
      (libsource (lib "eagle-import") (part "SFM-110-X1-XXX-D-LC"))
    )
    (comp (ref "CF3.2")
      (value "SFM-120-X1-XXX-D")
      (footprint "eagle-import:SFM-120-X1-XXX-D")
      (libsource (lib "eagle-import") (part "SFM-120-X1-XXX-D"))
    )
    (comp (ref "CM3.2")
      (value "J-MOLEX-SMPM-73300-0111X")
      (footprint "eagle-import:J-MOLEX-SMPM-73300-0111X")
      (libsource (lib "eagle-import") (part "J-MOLEX-SMPM-73300-0111X"))
    )
  )
  (nets
    (net (code "1") (name "AUX-1") (class "Default")
      (node (ref "CF2.1") (pin "1") (pinfunction "1_1") (pintype "passive"))
      (node (ref "CF2.1") (pin "2") (pinfunction "2_2") (pintype "passive"))
      (node (ref "CF3.1") (pin "1") (pinfunction "1_1") (pintype "passive"))
      (node (ref "CF3.1") (pin "2") (pinfunction "2_2") (pintype "passive"))
      (node (ref "CF4.1") (pin "1") (pinfunction "1_1") (pintype "passive"))
      (node (ref "CF4.1") (pin "2") (pinfunction "2_2") (pintype "passive"))
      (node (ref "CF7.1") (pin "1") (pinfunction "1_1") (pintype "passive"))
      (node (ref "CF7.1") (pin "2") (pinfunction "2_2") (pintype "passive"))
      (node (ref "CF8.1") (pin "1") (pinfunction "1_1") (pintype "passive"))
      (node (ref "CF8.1") (pin "2") (pinfunction "2_2") (pintype "passive"))
    )
    (net (code "2") (name "AUX-2") (class "Default")
      (node (ref "CF2.1") (pin "3") (pinfunction "3_3") (pintype "passive"))
      (node (ref "CF2.1") (pin "4") (pinfunction "4_4") (pintype "passive"))
      (node (ref "CF3.1") (pin "3") (pinfunction "3_3") (pintype "passive"))
      (node (ref "CF3.1") (pin "4") (pinfunction "4_4") (pintype "passive"))
      (node (ref "CF4.1") (pin "3") (pinfunction "3_3") (pintype "passive"))
      (node (ref "CF4.1") (pin "4") (pinfunction "4_4") (pintype "passive"))
      (node (ref "CF7.1") (pin "3") (pinfunction "3_3") (pintype "passive"))
      (node (ref "CF7.1") (pin "4") (pinfunction "4_4") (pintype "passive"))
      (node (ref "CF8.1") (pin "3") (pinfunction "3_3") (pintype "passive"))
      (node (ref "CF8.1") (pin "4") (pinfunction "4_4") (pintype "passive"))
    )
    (net (code "3") (name "AUX-3") (class "Default")
      (node (ref "CF2.1") (pin "5") (pinfunction "5_5") (pintype "passive"))
      (node (ref "CF2.1") (pin "6") (pinfunction "6_6") (pintype "passive"))
      (node (ref "CF3.1") (pin "5") (pinfunction "5_5") (pintype "passive"))
      (node (ref "CF3.1") (pin "6") (pinfunction "6_6") (pintype "passive"))
      (node (ref "CF4.1") (pin "5") (pinfunction "5_5") (pintype "passive"))
      (node (ref "CF4.1") (pin "6") (pinfunction "6_6") (pintype "passive"))
      (node (ref "CF7.1") (pin "5") (pinfunction "5_5") (pintype "passive"))
      (node (ref "CF7.1") (pin "6") (pinfunction "6_6") (pintype "passive"))
      (node (ref "CF8.1") (pin "5") (pinfunction "5_5") (pintype "passive"))
      (node (ref "CF8.1") (pin "6") (pinfunction "6_6") (pintype "passive"))
    )
    (net (code "4") (name "AUX-4") (class "Default")
      (node (ref "CF2.1") (pin "7") (pinfunction "7_7") (pintype "passive"))
      (node (ref "CF2.1") (pin "8") (pinfunction "8_8") (pintype "passive"))
      (node (ref "CF3.1") (pin "7") (pinfunction "7_7") (pintype "passive"))
      (node (ref "CF3.1") (pin "8") (pinfunction "8_8") (pintype "passive"))
      (node (ref "CF4.1") (pin "7") (pinfunction "7_7") (pintype "passive"))
      (node (ref "CF4.1") (pin "8") (pinfunction "8_8") (pintype "passive"))
      (node (ref "CF7.1") (pin "7") (pinfunction "7_7") (pintype "passive"))
      (node (ref "CF7.1") (pin "8") (pinfunction "8_8") (pintype "passive"))
      (node (ref "CF8.1") (pin "7") (pinfunction "7_7") (pintype "passive"))
      (node (ref "CF8.1") (pin "8") (pinfunction "8_8") (pintype "passive"))
    )
    (net (code "5") (name "AUX-5") (class "Default")
      (node (ref "CF2.1") (pin "10") (pinfunction "10_10") (pintype "passive"))
      (node (ref "CF2.1") (pin "9") (pinfunction "9_9") (pintype "passive"))
      (node (ref "CF3.1") (pin "10") (pinfunction "10_10") (pintype "passive"))
      (node (ref "CF3.1") (pin "9") (pinfunction "9_9") (pintype "passive"))
      (node (ref "CF4.1") (pin "10") (pinfunction "10_10") (pintype "passive"))
      (node (ref "CF4.1") (pin "9") (pinfunction "9_9") (pintype "passive"))
      (node (ref "CF7.1") (pin "10") (pinfunction "10_10") (pintype "passive"))
      (node (ref "CF7.1") (pin "9") (pinfunction "9_9") (pintype "passive"))
      (node (ref "CF8.1") (pin "10") (pinfunction "10_10") (pintype "passive"))
      (node (ref "CF8.1") (pin "9") (pinfunction "9_9") (pintype "passive"))
    )
    (net (code "6") (name "AUX-6") (class "Default")
      (node (ref "CF2.1") (pin "11") (pinfunction "11_11") (pintype "passive"))
      (node (ref "CF2.1") (pin "12") (pinfunction "12_12") (pintype "passive"))
      (node (ref "CF3.1") (pin "11") (pinfunction "11_11") (pintype "passive"))
      (node (ref "CF3.1") (pin "12") (pinfunction "12_12") (pintype "passive"))
      (node (ref "CF4.1") (pin "11") (pinfunction "11_11") (pintype "passive"))
      (node (ref "CF4.1") (pin "12") (pinfunction "12_12") (pintype "passive"))
      (node (ref "CF7.1") (pin "11") (pinfunction "11_11") (pintype "passive"))
      (node (ref "CF7.1") (pin "12") (pinfunction "12_12") (pintype "passive"))
      (node (ref "CF8.1") (pin "11") (pinfunction "11_11") (pintype "passive"))
      (node (ref "CF8.1") (pin "12") (pinfunction "12_12") (pintype "passive"))
    )
    (net (code "7") (name "AUX-7") (class "Default")
      (node (ref "CF2.1") (pin "13") (pinfunction "13_13") (pintype "passive"))
      (node (ref "CF2.1") (pin "14") (pinfunction "14_14") (pintype "passive"))
      (node (ref "CF3.1") (pin "13") (pinfunction "13_13") (pintype "passive"))
      (node (ref "CF3.1") (pin "14") (pinfunction "14_14") (pintype "passive"))
      (node (ref "CF4.1") (pin "13") (pinfunction "13_13") (pintype "passive"))
      (node (ref "CF4.1") (pin "14") (pinfunction "14_14") (pintype "passive"))
      (node (ref "CF7.1") (pin "13") (pinfunction "13_13") (pintype "passive"))
      (node (ref "CF7.1") (pin "14") (pinfunction "14_14") (pintype "passive"))
      (node (ref "CF8.1") (pin "13") (pinfunction "13_13") (pintype "passive"))
      (node (ref "CF8.1") (pin "14") (pinfunction "14_14") (pintype "passive"))
    )
    (net (code "8") (name "AUX-8") (class "Default")
      (node (ref "CF2.1") (pin "15") (pinfunction "15_15") (pintype "passive"))
      (node (ref "CF2.1") (pin "16") (pinfunction "16_16") (pintype "passive"))
      (node (ref "CF3.1") (pin "15") (pinfunction "15_15") (pintype "passive"))
      (node (ref "CF3.1") (pin "16") (pinfunction "16_16") (pintype "passive"))
      (node (ref "CF4.1") (pin "15") (pinfunction "15_15") (pintype "passive"))
      (node (ref "CF4.1") (pin "16") (pinfunction "16_16") (pintype "passive"))
      (node (ref "CF7.1") (pin "15") (pinfunction "15_15") (pintype "passive"))
      (node (ref "CF7.1") (pin "16") (pinfunction "16_16") (pintype "passive"))
      (node (ref "CF8.1") (pin "15") (pinfunction "15_15") (pintype "passive"))
      (node (ref "CF8.1") (pin "16") (pinfunction "16_16") (pintype "passive"))
    )
    (net (code "9") (name "AUX-9") (class "Default")
      (node (ref "CF2.1") (pin "17") (pinfunction "17_17") (pintype "passive"))
      (node (ref "CF2.1") (pin "18") (pinfunction "18_18") (pintype "passive"))
      (node (ref "CF3.1") (pin "17") (pinfunction "17_17") (pintype "passive"))
      (node (ref "CF3.1") (pin "18") (pinfunction "18_18") (pintype "passive"))
      (node (ref "CF4.1") (pin "17") (pinfunction "17_17") (pintype "passive"))
      (node (ref "CF4.1") (pin "18") (pinfunction "18_18") (pintype "passive"))
      (node (ref "CF7.1") (pin "17") (pinfunction "17_17") (pintype "passive"))
      (node (ref "CF7.1") (pin "18") (pinfunction "18_18") (pintype "passive"))
      (node (ref "CF8.1") (pin "17") (pinfunction "17_17") (pintype "passive"))
      (node (ref "CF8.1") (pin "18") (pinfunction "18_18") (pintype "passive"))
    )
    (net (code "10") (name "AUX-10") (class "Default")
      (node (ref "CF2.1") (pin "19") (pinfunction "19_19") (pintype "passive"))
      (node (ref "CF2.1") (pin "20") (pinfunction "20_20") (pintype "passive"))
      (node (ref "CF3.1") (pin "19") (pinfunction "19_19") (pintype "passive"))
      (node (ref "CF3.1") (pin "20") (pinfunction "20_20") (pintype "passive"))
      (node (ref "CF4.1") (pin "19") (pinfunction "19_19") (pintype "passive"))
      (node (ref "CF4.1") (pin "20") (pinfunction "20_20") (pintype "passive"))
      (node (ref "CF7.1") (pin "19") (pinfunction "19_19") (pintype "passive"))
      (node (ref "CF7.1") (pin "20") (pinfunction "20_20") (pintype "passive"))
      (node (ref "CF8.1") (pin "19") (pinfunction "19_19") (pintype "passive"))
      (node (ref "CF8.1") (pin "20") (pinfunction "20_20") (pintype "passive"))
    )
    (net (code "11") (name "CAN1_H") (class "Default")
      (node (ref "CF1.2") (pin "33") (pinfunction "33_33") (pintype "passive"))
      (node (ref "CF1.2") (pin "34") (pinfunction "34_34") (pintype "passive"))
      (node (ref "CF2.2") (pin "33") (pinfunction "33_33") (pintype "passive"))
      (node (ref "CF2.2") (pin "34") (pinfunction "34_34") (pintype "passive"))
      (node (ref "CF3.2") (pin "33") (pinfunction "33_33") (pintype "passive"))
      (node (ref "CF3.2") (pin "34") (pinfunction "34_34") (pintype "passive"))
      (node (ref "CF4.2") (pin "33") (pinfunction "33_33") (pintype "passive"))
      (node (ref "CF4.2") (pin "34") (pinfunction "34_34") (pintype "passive"))
      (node (ref "CF5.2") (pin "33") (pinfunction "33_33") (pintype "passive"))
      (node (ref "CF5.2") (pin "34") (pinfunction "34_34") (pintype "passive"))
      (node (ref "CF6.2") (pin "33") (pinfunction "33_33") (pintype "passive"))
      (node (ref "CF6.2") (pin "34") (pinfunction "34_34") (pintype "passive"))
      (node (ref "CF7.2") (pin "33") (pinfunction "33_33") (pintype "passive"))
      (node (ref "CF7.2") (pin "34") (pinfunction "34_34") (pintype "passive"))
      (node (ref "CF8.2") (pin "33") (pinfunction "33_33") (pintype "passive"))
      (node (ref "CF8.2") (pin "34") (pinfunction "34_34") (pintype "passive"))
      (node (ref "J3") (pin "17") (pinfunction "17_17") (pintype "passive"))
      (node (ref "R1") (pin "1") (pinfunction "1_1") (pintype "passive"))
      (node (ref "R5") (pin "1") (pinfunction "1_1") (pintype "passive"))
    )
    (net (code "12") (name "CAN1_L") (class "Default")
      (node (ref "CF1.2") (pin "35") (pinfunction "35_35") (pintype "passive"))
      (node (ref "CF1.2") (pin "36") (pinfunction "36_36") (pintype "passive"))
      (node (ref "CF2.2") (pin "35") (pinfunction "35_35") (pintype "passive"))
      (node (ref "CF2.2") (pin "36") (pinfunction "36_36") (pintype "passive"))
      (node (ref "CF3.2") (pin "35") (pinfunction "35_35") (pintype "passive"))
      (node (ref "CF3.2") (pin "36") (pinfunction "36_36") (pintype "passive"))
      (node (ref "CF4.2") (pin "35") (pinfunction "35_35") (pintype "passive"))
      (node (ref "CF4.2") (pin "36") (pinfunction "36_36") (pintype "passive"))
      (node (ref "CF5.2") (pin "35") (pinfunction "35_35") (pintype "passive"))
      (node (ref "CF5.2") (pin "36") (pinfunction "36_36") (pintype "passive"))
      (node (ref "CF6.2") (pin "35") (pinfunction "35_35") (pintype "passive"))
      (node (ref "CF6.2") (pin "36") (pinfunction "36_36") (pintype "passive"))
      (node (ref "CF7.2") (pin "35") (pinfunction "35_35") (pintype "passive"))
      (node (ref "CF7.2") (pin "36") (pinfunction "36_36") (pintype "passive"))
      (node (ref "CF8.2") (pin "35") (pinfunction "35_35") (pintype "passive"))
      (node (ref "CF8.2") (pin "36") (pinfunction "36_36") (pintype "passive"))
      (node (ref "J3") (pin "18") (pinfunction "18_18") (pintype "passive"))
      (node (ref "R2") (pin "1") (pinfunction "1_1") (pintype "passive"))
      (node (ref "R6") (pin "1") (pinfunction "1_1") (pintype "passive"))
    )
    (net (code "13") (name "CAN2_H") (class "Default")
      (node (ref "CF1.2") (pin "17") (pinfunction "17_17") (pintype "passive"))
      (node (ref "CF1.2") (pin "18") (pinfunction "18_18") (pintype "passive"))
      (node (ref "CF2.2") (pin "17") (pinfunction "17_17") (pintype "passive"))
      (node (ref "CF2.2") (pin "18") (pinfunction "18_18") (pintype "passive"))
      (node (ref "CF3.2") (pin "17") (pinfunction "17_17") (pintype "passive"))
      (node (ref "CF3.2") (pin "18") (pinfunction "18_18") (pintype "passive"))
      (node (ref "CF4.2") (pin "17") (pinfunction "17_17") (pintype "passive"))
      (node (ref "CF4.2") (pin "18") (pinfunction "18_18") (pintype "passive"))
      (node (ref "CF5.2") (pin "17") (pinfunction "17_17") (pintype "passive"))
      (node (ref "CF5.2") (pin "18") (pinfunction "18_18") (pintype "passive"))
      (node (ref "CF6.2") (pin "17") (pinfunction "17_17") (pintype "passive"))
      (node (ref "CF6.2") (pin "18") (pinfunction "18_18") (pintype "passive"))
      (node (ref "CF7.2") (pin "17") (pinfunction "17_17") (pintype "passive"))
      (node (ref "CF7.2") (pin "18") (pinfunction "18_18") (pintype "passive"))
      (node (ref "CF8.2") (pin "17") (pinfunction "17_17") (pintype "passive"))
      (node (ref "CF8.2") (pin "18") (pinfunction "18_18") (pintype "passive"))
      (node (ref "J3") (pin "9") (pinfunction "9_9") (pintype "passive"))
      (node (ref "R3") (pin "1") (pinfunction "1_1") (pintype "passive"))
      (node (ref "R7") (pin "1") (pinfunction "1_1") (pintype "passive"))
    )
    (net (code "14") (name "CAN2_L") (class "Default")
      (node (ref "CF1.2") (pin "19") (pinfunction "19_19") (pintype "passive"))
      (node (ref "CF1.2") (pin "20") (pinfunction "20_20") (pintype "passive"))
      (node (ref "CF2.2") (pin "19") (pinfunction "19_19") (pintype "passive"))
      (node (ref "CF2.2") (pin "20") (pinfunction "20_20") (pintype "passive"))
      (node (ref "CF3.2") (pin "19") (pinfunction "19_19") (pintype "passive"))
      (node (ref "CF3.2") (pin "20") (pinfunction "20_20") (pintype "passive"))
      (node (ref "CF4.2") (pin "19") (pinfunction "19_19") (pintype "passive"))
      (node (ref "CF4.2") (pin "20") (pinfunction "20_20") (pintype "passive"))
      (node (ref "CF5.2") (pin "19") (pinfunction "19_19") (pintype "passive"))
      (node (ref "CF5.2") (pin "20") (pinfunction "20_20") (pintype "passive"))
      (node (ref "CF6.2") (pin "19") (pinfunction "19_19") (pintype "passive"))
      (node (ref "CF6.2") (pin "20") (pinfunction "20_20") (pintype "passive"))
      (node (ref "CF7.2") (pin "19") (pinfunction "19_19") (pintype "passive"))
      (node (ref "CF7.2") (pin "20") (pinfunction "20_20") (pintype "passive"))
      (node (ref "CF8.2") (pin "19") (pinfunction "19_19") (pintype "passive"))
      (node (ref "CF8.2") (pin "20") (pinfunction "20_20") (pintype "passive"))
      (node (ref "J3") (pin "10") (pinfunction "10_10") (pintype "passive"))
      (node (ref "R4") (pin "1") (pinfunction "1_1") (pintype "passive"))
      (node (ref "R8") (pin "1") (pinfunction "1_1") (pintype "passive"))
    )
    (net (code "15") (name "GND") (class "Default")
      (node (ref "C1") (pin "2") (pinfunction "2_2") (pintype "passive"))
      (node (ref "C2") (pin "2") (pinfunction "2_2") (pintype "passive"))
      (node (ref "C3") (pin "2") (pinfunction "2_2") (pintype "passive"))
      (node (ref "C4") (pin "2") (pinfunction "2_2") (pintype "passive"))
      (node (ref "CF1.2") (pin "27") (pinfunction "27_27") (pintype "passive"))
      (node (ref "CF1.2") (pin "28") (pinfunction "28_28") (pintype "passive"))
      (node (ref "CF1.2") (pin "29") (pinfunction "29_29") (pintype "passive"))
      (node (ref "CF1.2") (pin "30") (pinfunction "30_30") (pintype "passive"))
      (node (ref "CF1.2") (pin "31") (pinfunction "31_31") (pintype "passive"))
      (node (ref "CF1.2") (pin "32") (pinfunction "32_32") (pintype "passive"))
      (node (ref "CF1.2") (pin "37") (pinfunction "37_37") (pintype "passive"))
      (node (ref "CF1.2") (pin "38") (pinfunction "38_38") (pintype "passive"))
      (node (ref "CF1.2") (pin "LC1") (pinfunction "LC1_LC1") (pintype "passive"))
      (node (ref "CF1.2") (pin "LC2") (pinfunction "LC2_LC2") (pintype "passive"))
      (node (ref "CF2.1") (pin "LC1") (pinfunction "LC1_LC1") (pintype "passive"))
      (node (ref "CF2.1") (pin "LC2") (pinfunction "LC2_LC2") (pintype "passive"))
      (node (ref "CF2.2") (pin "27") (pinfunction "27_27") (pintype "passive"))
      (node (ref "CF2.2") (pin "28") (pinfunction "28_28") (pintype "passive"))
      (node (ref "CF2.2") (pin "29") (pinfunction "29_29") (pintype "passive"))
      (node (ref "CF2.2") (pin "30") (pinfunction "30_30") (pintype "passive"))
      (node (ref "CF2.2") (pin "31") (pinfunction "31_31") (pintype "passive"))
      (node (ref "CF2.2") (pin "32") (pinfunction "32_32") (pintype "passive"))
      (node (ref "CF2.2") (pin "37") (pinfunction "37_37") (pintype "passive"))
      (node (ref "CF2.2") (pin "38") (pinfunction "38_38") (pintype "passive"))
      (node (ref "CF2.2") (pin "LC1") (pinfunction "LC1_LC1") (pintype "passive"))
      (node (ref "CF2.2") (pin "LC2") (pinfunction "LC2_LC2") (pintype "passive"))
      (node (ref "CF3.1") (pin "LC1") (pinfunction "LC1_LC1") (pintype "passive"))
      (node (ref "CF3.1") (pin "LC2") (pinfunction "LC2_LC2") (pintype "passive"))
      (node (ref "CF3.2") (pin "27") (pinfunction "27_27") (pintype "passive"))
      (node (ref "CF3.2") (pin "28") (pinfunction "28_28") (pintype "passive"))
      (node (ref "CF3.2") (pin "29") (pinfunction "29_29") (pintype "passive"))
      (node (ref "CF3.2") (pin "30") (pinfunction "30_30") (pintype "passive"))
      (node (ref "CF3.2") (pin "31") (pinfunction "31_31") (pintype "passive"))
      (node (ref "CF3.2") (pin "32") (pinfunction "32_32") (pintype "passive"))
      (node (ref "CF3.2") (pin "37") (pinfunction "37_37") (pintype "passive"))
      (node (ref "CF3.2") (pin "38") (pinfunction "38_38") (pintype "passive"))
      (node (ref "CF3.2") (pin "LC1") (pinfunction "LC1_LC1") (pintype "passive"))
      (node (ref "CF3.2") (pin "LC2") (pinfunction "LC2_LC2") (pintype "passive"))
      (node (ref "CF4.1") (pin "LC1") (pinfunction "LC1_LC1") (pintype "passive"))
      (node (ref "CF4.1") (pin "LC2") (pinfunction "LC2_LC2") (pintype "passive"))
      (node (ref "CF4.2") (pin "27") (pinfunction "27_27") (pintype "passive"))
      (node (ref "CF4.2") (pin "28") (pinfunction "28_28") (pintype "passive"))
      (node (ref "CF4.2") (pin "29") (pinfunction "29_29") (pintype "passive"))
      (node (ref "CF4.2") (pin "30") (pinfunction "30_30") (pintype "passive"))
      (node (ref "CF4.2") (pin "31") (pinfunction "31_31") (pintype "passive"))
      (node (ref "CF4.2") (pin "32") (pinfunction "32_32") (pintype "passive"))
      (node (ref "CF4.2") (pin "37") (pinfunction "37_37") (pintype "passive"))
      (node (ref "CF4.2") (pin "38") (pinfunction "38_38") (pintype "passive"))
      (node (ref "CF4.2") (pin "LC1") (pinfunction "LC1_LC1") (pintype "passive"))
      (node (ref "CF4.2") (pin "LC2") (pinfunction "LC2_LC2") (pintype "passive"))
      (node (ref "CF5.2") (pin "27") (pinfunction "27_27") (pintype "passive"))
      (node (ref "CF5.2") (pin "28") (pinfunction "28_28") (pintype "passive"))
      (node (ref "CF5.2") (pin "29") (pinfunction "29_29") (pintype "passive"))
      (node (ref "CF5.2") (pin "30") (pinfunction "30_30") (pintype "passive"))
      (node (ref "CF5.2") (pin "31") (pinfunction "31_31") (pintype "passive"))
      (node (ref "CF5.2") (pin "32") (pinfunction "32_32") (pintype "passive"))
      (node (ref "CF5.2") (pin "37") (pinfunction "37_37") (pintype "passive"))
      (node (ref "CF5.2") (pin "38") (pinfunction "38_38") (pintype "passive"))
      (node (ref "CF5.2") (pin "LC1") (pinfunction "LC1_LC1") (pintype "passive"))
      (node (ref "CF5.2") (pin "LC2") (pinfunction "LC2_LC2") (pintype "passive"))
      (node (ref "CF6.2") (pin "27") (pinfunction "27_27") (pintype "passive"))
      (node (ref "CF6.2") (pin "28") (pinfunction "28_28") (pintype "passive"))
      (node (ref "CF6.2") (pin "29") (pinfunction "29_29") (pintype "passive"))
      (node (ref "CF6.2") (pin "30") (pinfunction "30_30") (pintype "passive"))
      (node (ref "CF6.2") (pin "31") (pinfunction "31_31") (pintype "passive"))
      (node (ref "CF6.2") (pin "32") (pinfunction "32_32") (pintype "passive"))
      (node (ref "CF6.2") (pin "37") (pinfunction "37_37") (pintype "passive"))
      (node (ref "CF6.2") (pin "38") (pinfunction "38_38") (pintype "passive"))
      (node (ref "CF6.2") (pin "LC1") (pinfunction "LC1_LC1") (pintype "passive"))
      (node (ref "CF6.2") (pin "LC2") (pinfunction "LC2_LC2") (pintype "passive"))
      (node (ref "CF7.1") (pin "LC1") (pinfunction "LC1_LC1") (pintype "passive"))
      (node (ref "CF7.1") (pin "LC2") (pinfunction "LC2_LC2") (pintype "passive"))
      (node (ref "CF7.2") (pin "27") (pinfunction "27_27") (pintype "passive"))
      (node (ref "CF7.2") (pin "28") (pinfunction "28_28") (pintype "passive"))
      (node (ref "CF7.2") (pin "29") (pinfunction "29_29") (pintype "passive"))
      (node (ref "CF7.2") (pin "30") (pinfunction "30_30") (pintype "passive"))
      (node (ref "CF7.2") (pin "31") (pinfunction "31_31") (pintype "passive"))
      (node (ref "CF7.2") (pin "32") (pinfunction "32_32") (pintype "passive"))
      (node (ref "CF7.2") (pin "37") (pinfunction "37_37") (pintype "passive"))
      (node (ref "CF7.2") (pin "38") (pinfunction "38_38") (pintype "passive"))
      (node (ref "CF7.2") (pin "LC1") (pinfunction "LC1_LC1") (pintype "passive"))
      (node (ref "CF7.2") (pin "LC2") (pinfunction "LC2_LC2") (pintype "passive"))
      (node (ref "CF8.1") (pin "LC1") (pinfunction "LC1_LC1") (pintype "passive"))
      (node (ref "CF8.1") (pin "LC2") (pinfunction "LC2_LC2") (pintype "passive"))
      (node (ref "CF8.2") (pin "27") (pinfunction "27_27") (pintype "passive"))
      (node (ref "CF8.2") (pin "28") (pinfunction "28_28") (pintype "passive"))
      (node (ref "CF8.2") (pin "29") (pinfunction "29_29") (pintype "passive"))
      (node (ref "CF8.2") (pin "30") (pinfunction "30_30") (pintype "passive"))
      (node (ref "CF8.2") (pin "31") (pinfunction "31_31") (pintype "passive"))
      (node (ref "CF8.2") (pin "32") (pinfunction "32_32") (pintype "passive"))
      (node (ref "CF8.2") (pin "37") (pinfunction "37_37") (pintype "passive"))
      (node (ref "CF8.2") (pin "38") (pinfunction "38_38") (pintype "passive"))
      (node (ref "CF8.2") (pin "LC1") (pinfunction "LC1_LC1") (pintype "passive"))
      (node (ref "CF8.2") (pin "LC2") (pinfunction "LC2_LC2") (pintype "passive"))
      (node (ref "CM1.1") (pin "P$1") (pinfunction "SHIELD1_P$1") (pintype "passive"))
      (node (ref "CM1.1") (pin "P$2") (pinfunction "SHIELD1_P$2") (pintype "passive"))
      (node (ref "CM1.1") (pin "P$3") (pinfunction "SHIELD1_P$3") (pintype "passive"))
      (node (ref "CM1.1") (pin "P$4") (pinfunction "SHIELD1_P$4") (pintype "passive"))
      (node (ref "CM1.2") (pin "P$1") (pinfunction "SHIELD1_P$1") (pintype "passive"))
      (node (ref "CM1.2") (pin "P$2") (pinfunction "SHIELD1_P$2") (pintype "passive"))
      (node (ref "CM1.2") (pin "P$3") (pinfunction "SHIELD1_P$3") (pintype "passive"))
      (node (ref "CM1.2") (pin "P$4") (pinfunction "SHIELD1_P$4") (pintype "passive"))
      (node (ref "CM1.3") (pin "P$1") (pinfunction "SHIELD1_P$1") (pintype "passive"))
      (node (ref "CM1.3") (pin "P$2") (pinfunction "SHIELD1_P$2") (pintype "passive"))
      (node (ref "CM1.3") (pin "P$3") (pinfunction "SHIELD1_P$3") (pintype "passive"))
      (node (ref "CM1.3") (pin "P$4") (pinfunction "SHIELD1_P$4") (pintype "passive"))
      (node (ref "CM2.1") (pin "P$1") (pinfunction "SHIELD1_P$1") (pintype "passive"))
      (node (ref "CM2.1") (pin "P$2") (pinfunction "SHIELD1_P$2") (pintype "passive"))
      (node (ref "CM2.1") (pin "P$3") (pinfunction "SHIELD1_P$3") (pintype "passive"))
      (node (ref "CM2.1") (pin "P$4") (pinfunction "SHIELD1_P$4") (pintype "passive"))
      (node (ref "CM2.2") (pin "P$1") (pinfunction "SHIELD1_P$1") (pintype "passive"))
      (node (ref "CM2.2") (pin "P$2") (pinfunction "SHIELD1_P$2") (pintype "passive"))
      (node (ref "CM2.2") (pin "P$3") (pinfunction "SHIELD1_P$3") (pintype "passive"))
      (node (ref "CM2.2") (pin "P$4") (pinfunction "SHIELD1_P$4") (pintype "passive"))
      (node (ref "CM2.3") (pin "P$1") (pinfunction "SHIELD1_P$1") (pintype "passive"))
      (node (ref "CM2.3") (pin "P$2") (pinfunction "SHIELD1_P$2") (pintype "passive"))
      (node (ref "CM2.3") (pin "P$3") (pinfunction "SHIELD1_P$3") (pintype "passive"))
      (node (ref "CM2.3") (pin "P$4") (pinfunction "SHIELD1_P$4") (pintype "passive"))
      (node (ref "CM3.2") (pin "P$1") (pinfunction "SHIELD1_P$1") (pintype "passive"))
      (node (ref "CM3.2") (pin "P$2") (pinfunction "SHIELD1_P$2") (pintype "passive"))
      (node (ref "CM3.2") (pin "P$3") (pinfunction "SHIELD1_P$3") (pintype "passive"))
      (node (ref "CM3.2") (pin "P$4") (pinfunction "SHIELD1_P$4") (pintype "passive"))
      (node (ref "CM4.1") (pin "P$1") (pinfunction "SHIELD1_P$1") (pintype "passive"))
      (node (ref "CM4.1") (pin "P$2") (pinfunction "SHIELD1_P$2") (pintype "passive"))
      (node (ref "CM4.1") (pin "P$3") (pinfunction "SHIELD1_P$3") (pintype "passive"))
      (node (ref "CM4.1") (pin "P$4") (pinfunction "SHIELD1_P$4") (pintype "passive"))
      (node (ref "J1") (pin "1") (pinfunction "1_1") (pintype "passive"))
      (node (ref "J1") (pin "10") (pinfunction "10_10") (pintype "passive"))
      (node (ref "J1") (pin "11") (pinfunction "11_11") (pintype "passive"))
      (node (ref "J1") (pin "12") (pinfunction "12_12") (pintype "passive"))
      (node (ref "J1") (pin "2") (pinfunction "2_2") (pintype "passive"))
      (node (ref "J1") (pin "3") (pinfunction "3_3") (pintype "passive"))
      (node (ref "J1") (pin "4") (pinfunction "4_4") (pintype "passive"))
      (node (ref "J1") (pin "5") (pinfunction "5_5") (pintype "passive"))
      (node (ref "J1") (pin "6") (pinfunction "6_6") (pintype "passive"))
      (node (ref "J1") (pin "7") (pinfunction "7_7") (pintype "passive"))
      (node (ref "J1") (pin "8") (pinfunction "8_8") (pintype "passive"))
      (node (ref "J1") (pin "9") (pinfunction "9_9") (pintype "passive"))
      (node (ref "J1") (pin "HD1") (pinfunction "HD_HD1") (pintype "passive"))
      (node (ref "J1") (pin "HD2") (pinfunction "HD_HD2") (pintype "passive"))
      (node (ref "J1") (pin "HD3") (pinfunction "HD_HD3") (pintype "passive"))
      (node (ref "J3") (pin "14") (pinfunction "14_14") (pintype "passive"))
      (node (ref "J3") (pin "15") (pinfunction "15_15") (pintype "passive"))
      (node (ref "J3") (pin "16") (pinfunction "16_16") (pintype "passive"))
      (node (ref "J3") (pin "19") (pinfunction "19_19") (pintype "passive"))
    )
    (net (code "16") (name "L-GPS") (class "Default")
      (node (ref "CM2.1") (pin "RF-DOWN") (pinfunction "RF_RF-DOWN") (pintype "passive"))
      (node (ref "CM3.2") (pin "RF-DOWN") (pinfunction "RF_RF-DOWN") (pintype "passive"))
    )
    (net (code "17") (name "L-TURNSTILE") (class "Default")
      (node (ref "CM1.2") (pin "RF-DOWN") (pinfunction "RF_RF-DOWN") (pintype "passive"))
      (node (ref "CM2.2") (pin "RF-DOWN") (pinfunction "RF_RF-DOWN") (pintype "passive"))
    )
    (net (code "18") (name "Net-(C1-Pad1)") (class "Default")
      (node (ref "C1") (pin "1") (pinfunction "1_1") (pintype "passive"))
      (node (ref "R1") (pin "2") (pinfunction "2_2") (pintype "passive"))
      (node (ref "R2") (pin "2") (pinfunction "2_2") (pintype "passive"))
    )
    (net (code "19") (name "Net-(C2-Pad1)") (class "Default")
      (node (ref "C2") (pin "1") (pinfunction "1_1") (pintype "passive"))
      (node (ref "R3") (pin "2") (pinfunction "2_2") (pintype "passive"))
      (node (ref "R4") (pin "2") (pinfunction "2_2") (pintype "passive"))
    )
    (net (code "20") (name "Net-(C3-Pad1)") (class "Default")
      (node (ref "C3") (pin "1") (pinfunction "1_1") (pintype "passive"))
      (node (ref "R5") (pin "2") (pinfunction "2_2") (pintype "passive"))
      (node (ref "R6") (pin "2") (pinfunction "2_2") (pintype "passive"))
    )
    (net (code "21") (name "Net-(C4-Pad1)") (class "Default")
      (node (ref "C4") (pin "1") (pinfunction "1_1") (pintype "passive"))
      (node (ref "R7") (pin "2") (pinfunction "2_2") (pintype "passive"))
      (node (ref "R8") (pin "2") (pinfunction "2_2") (pintype "passive"))
    )
    (net (code "22") (name "OPD_PWR") (class "Default")
      (node (ref "CF1.2") (pin "15") (pinfunction "15_15") (pintype "passive"))
      (node (ref "CF1.2") (pin "16") (pinfunction "16_16") (pintype "passive"))
      (node (ref "CF2.2") (pin "15") (pinfunction "15_15") (pintype "passive"))
      (node (ref "CF2.2") (pin "16") (pinfunction "16_16") (pintype "passive"))
      (node (ref "CF3.2") (pin "15") (pinfunction "15_15") (pintype "passive"))
      (node (ref "CF3.2") (pin "16") (pinfunction "16_16") (pintype "passive"))
      (node (ref "CF4.2") (pin "15") (pinfunction "15_15") (pintype "passive"))
      (node (ref "CF4.2") (pin "16") (pinfunction "16_16") (pintype "passive"))
      (node (ref "CF5.2") (pin "15") (pinfunction "15_15") (pintype "passive"))
      (node (ref "CF5.2") (pin "16") (pinfunction "16_16") (pintype "passive"))
      (node (ref "CF6.2") (pin "15") (pinfunction "15_15") (pintype "passive"))
      (node (ref "CF6.2") (pin "16") (pinfunction "16_16") (pintype "passive"))
      (node (ref "CF7.2") (pin "15") (pinfunction "15_15") (pintype "passive"))
      (node (ref "CF7.2") (pin "16") (pinfunction "16_16") (pintype "passive"))
      (node (ref "CF8.2") (pin "15") (pinfunction "15_15") (pintype "passive"))
      (node (ref "CF8.2") (pin "16") (pinfunction "16_16") (pintype "passive"))
      (node (ref "J3") (pin "8") (pinfunction "8_8") (pintype "passive"))
    )
    (net (code "23") (name "OPD_SCL") (class "Default")
      (node (ref "CF1.2") (pin "13") (pinfunction "13_13") (pintype "passive"))
      (node (ref "CF1.2") (pin "14") (pinfunction "14_14") (pintype "passive"))
      (node (ref "CF2.2") (pin "13") (pinfunction "13_13") (pintype "passive"))
      (node (ref "CF2.2") (pin "14") (pinfunction "14_14") (pintype "passive"))
      (node (ref "CF3.2") (pin "13") (pinfunction "13_13") (pintype "passive"))
      (node (ref "CF3.2") (pin "14") (pinfunction "14_14") (pintype "passive"))
      (node (ref "CF4.2") (pin "13") (pinfunction "13_13") (pintype "passive"))
      (node (ref "CF4.2") (pin "14") (pinfunction "14_14") (pintype "passive"))
      (node (ref "CF5.2") (pin "13") (pinfunction "13_13") (pintype "passive"))
      (node (ref "CF5.2") (pin "14") (pinfunction "14_14") (pintype "passive"))
      (node (ref "CF6.2") (pin "13") (pinfunction "13_13") (pintype "passive"))
      (node (ref "CF6.2") (pin "14") (pinfunction "14_14") (pintype "passive"))
      (node (ref "CF7.2") (pin "13") (pinfunction "13_13") (pintype "passive"))
      (node (ref "CF7.2") (pin "14") (pinfunction "14_14") (pintype "passive"))
      (node (ref "CF8.2") (pin "13") (pinfunction "13_13") (pintype "passive"))
      (node (ref "CF8.2") (pin "14") (pinfunction "14_14") (pintype "passive"))
      (node (ref "J3") (pin "7") (pinfunction "7_7") (pintype "passive"))
    )
    (net (code "24") (name "OPD_SDA") (class "Default")
      (node (ref "CF1.2") (pin "11") (pinfunction "11_11") (pintype "passive"))
      (node (ref "CF1.2") (pin "12") (pinfunction "12_12") (pintype "passive"))
      (node (ref "CF2.2") (pin "11") (pinfunction "11_11") (pintype "passive"))
      (node (ref "CF2.2") (pin "12") (pinfunction "12_12") (pintype "passive"))
      (node (ref "CF3.2") (pin "11") (pinfunction "11_11") (pintype "passive"))
      (node (ref "CF3.2") (pin "12") (pinfunction "12_12") (pintype "passive"))
      (node (ref "CF4.2") (pin "11") (pinfunction "11_11") (pintype "passive"))
      (node (ref "CF4.2") (pin "12") (pinfunction "12_12") (pintype "passive"))
      (node (ref "CF5.2") (pin "11") (pinfunction "11_11") (pintype "passive"))
      (node (ref "CF5.2") (pin "12") (pinfunction "12_12") (pintype "passive"))
      (node (ref "CF6.2") (pin "11") (pinfunction "11_11") (pintype "passive"))
      (node (ref "CF6.2") (pin "12") (pinfunction "12_12") (pintype "passive"))
      (node (ref "CF7.2") (pin "11") (pinfunction "11_11") (pintype "passive"))
      (node (ref "CF7.2") (pin "12") (pinfunction "12_12") (pintype "passive"))
      (node (ref "CF8.2") (pin "11") (pinfunction "11_11") (pintype "passive"))
      (node (ref "CF8.2") (pin "12") (pinfunction "12_12") (pintype "passive"))
      (node (ref "J3") (pin "6") (pinfunction "6_6") (pintype "passive"))
    )
    (net (code "25") (name "S-TURNSTILE") (class "Default")
      (node (ref "CM1.1") (pin "RF-DOWN") (pinfunction "RF_RF-DOWN") (pintype "passive"))
      (node (ref "CM4.1") (pin "RF-DOWN") (pinfunction "RF_RF-DOWN") (pintype "passive"))
    )
    (net (code "26") (name "SPARE1-TURNSTILE-DPLY") (class "Default")
      (node (ref "CF1.2") (pin "10") (pinfunction "10_10") (pintype "passive"))
      (node (ref "CF1.2") (pin "9") (pinfunction "9_9") (pintype "passive"))
      (node (ref "CF2.2") (pin "10") (pinfunction "10_10") (pintype "passive"))
      (node (ref "CF2.2") (pin "9") (pinfunction "9_9") (pintype "passive"))
      (node (ref "CF3.2") (pin "10") (pinfunction "10_10") (pintype "passive"))
      (node (ref "CF3.2") (pin "9") (pinfunction "9_9") (pintype "passive"))
      (node (ref "CF4.2") (pin "10") (pinfunction "10_10") (pintype "passive"))
      (node (ref "CF4.2") (pin "9") (pinfunction "9_9") (pintype "passive"))
      (node (ref "CF5.2") (pin "10") (pinfunction "10_10") (pintype "passive"))
      (node (ref "CF5.2") (pin "9") (pinfunction "9_9") (pintype "passive"))
      (node (ref "CF6.2") (pin "10") (pinfunction "10_10") (pintype "passive"))
      (node (ref "CF6.2") (pin "9") (pinfunction "9_9") (pintype "passive"))
      (node (ref "CF7.2") (pin "10") (pinfunction "10_10") (pintype "passive"))
      (node (ref "CF7.2") (pin "9") (pinfunction "9_9") (pintype "passive"))
      (node (ref "CF8.2") (pin "10") (pinfunction "10_10") (pintype "passive"))
      (node (ref "CF8.2") (pin "9") (pinfunction "9_9") (pintype "passive"))
      (node (ref "J3") (pin "5") (pinfunction "5_5") (pintype "passive"))
    )
    (net (code "27") (name "SPARE2") (class "Default")
      (node (ref "CF1.2") (pin "7") (pinfunction "7_7") (pintype "passive"))
      (node (ref "CF1.2") (pin "8") (pinfunction "8_8") (pintype "passive"))
      (node (ref "CF2.2") (pin "7") (pinfunction "7_7") (pintype "passive"))
      (node (ref "CF2.2") (pin "8") (pinfunction "8_8") (pintype "passive"))
      (node (ref "CF3.2") (pin "7") (pinfunction "7_7") (pintype "passive"))
      (node (ref "CF3.2") (pin "8") (pinfunction "8_8") (pintype "passive"))
      (node (ref "CF4.2") (pin "7") (pinfunction "7_7") (pintype "passive"))
      (node (ref "CF4.2") (pin "8") (pinfunction "8_8") (pintype "passive"))
      (node (ref "CF5.2") (pin "7") (pinfunction "7_7") (pintype "passive"))
      (node (ref "CF5.2") (pin "8") (pinfunction "8_8") (pintype "passive"))
      (node (ref "CF6.2") (pin "7") (pinfunction "7_7") (pintype "passive"))
      (node (ref "CF6.2") (pin "8") (pinfunction "8_8") (pintype "passive"))
      (node (ref "CF7.2") (pin "7") (pinfunction "7_7") (pintype "passive"))
      (node (ref "CF7.2") (pin "8") (pinfunction "8_8") (pintype "passive"))
      (node (ref "CF8.2") (pin "7") (pinfunction "7_7") (pintype "passive"))
      (node (ref "CF8.2") (pin "8") (pinfunction "8_8") (pintype "passive"))
      (node (ref "J1") (pin "13") (pinfunction "13_13") (pintype "passive"))
      (node (ref "J1") (pin "14") (pinfunction "14_14") (pintype "passive"))
      (node (ref "J3") (pin "4") (pinfunction "4_4") (pintype "passive"))
    )
    (net (code "28") (name "SPARE3-MAG-PWR") (class "Default")
      (node (ref "CF1.2") (pin "5") (pinfunction "5_5") (pintype "passive"))
      (node (ref "CF1.2") (pin "6") (pinfunction "6_6") (pintype "passive"))
      (node (ref "CF2.2") (pin "5") (pinfunction "5_5") (pintype "passive"))
      (node (ref "CF2.2") (pin "6") (pinfunction "6_6") (pintype "passive"))
      (node (ref "CF3.2") (pin "5") (pinfunction "5_5") (pintype "passive"))
      (node (ref "CF3.2") (pin "6") (pinfunction "6_6") (pintype "passive"))
      (node (ref "CF4.2") (pin "5") (pinfunction "5_5") (pintype "passive"))
      (node (ref "CF4.2") (pin "6") (pinfunction "6_6") (pintype "passive"))
      (node (ref "CF5.2") (pin "5") (pinfunction "5_5") (pintype "passive"))
      (node (ref "CF5.2") (pin "6") (pinfunction "6_6") (pintype "passive"))
      (node (ref "CF6.2") (pin "5") (pinfunction "5_5") (pintype "passive"))
      (node (ref "CF6.2") (pin "6") (pinfunction "6_6") (pintype "passive"))
      (node (ref "CF7.2") (pin "5") (pinfunction "5_5") (pintype "passive"))
      (node (ref "CF7.2") (pin "6") (pinfunction "6_6") (pintype "passive"))
      (node (ref "CF8.2") (pin "5") (pinfunction "5_5") (pintype "passive"))
      (node (ref "CF8.2") (pin "6") (pinfunction "6_6") (pintype "passive"))
      (node (ref "J1") (pin "15") (pinfunction "15_15") (pintype "passive"))
      (node (ref "J1") (pin "16") (pinfunction "16_16") (pintype "passive"))
      (node (ref "J3") (pin "3") (pinfunction "3_3") (pintype "passive"))
    )
    (net (code "29") (name "SPARE4-MAG-SCL") (class "Default")
      (node (ref "CF1.2") (pin "3") (pinfunction "3_3") (pintype "passive"))
      (node (ref "CF1.2") (pin "4") (pinfunction "4_4") (pintype "passive"))
      (node (ref "CF2.2") (pin "3") (pinfunction "3_3") (pintype "passive"))
      (node (ref "CF2.2") (pin "4") (pinfunction "4_4") (pintype "passive"))
      (node (ref "CF3.2") (pin "3") (pinfunction "3_3") (pintype "passive"))
      (node (ref "CF3.2") (pin "4") (pinfunction "4_4") (pintype "passive"))
      (node (ref "CF4.2") (pin "3") (pinfunction "3_3") (pintype "passive"))
      (node (ref "CF4.2") (pin "4") (pinfunction "4_4") (pintype "passive"))
      (node (ref "CF5.2") (pin "3") (pinfunction "3_3") (pintype "passive"))
      (node (ref "CF5.2") (pin "4") (pinfunction "4_4") (pintype "passive"))
      (node (ref "CF6.2") (pin "3") (pinfunction "3_3") (pintype "passive"))
      (node (ref "CF6.2") (pin "4") (pinfunction "4_4") (pintype "passive"))
      (node (ref "CF7.2") (pin "3") (pinfunction "3_3") (pintype "passive"))
      (node (ref "CF7.2") (pin "4") (pinfunction "4_4") (pintype "passive"))
      (node (ref "CF8.2") (pin "3") (pinfunction "3_3") (pintype "passive"))
      (node (ref "CF8.2") (pin "4") (pinfunction "4_4") (pintype "passive"))
      (node (ref "J1") (pin "17") (pinfunction "17_17") (pintype "passive"))
      (node (ref "J1") (pin "18") (pinfunction "18_18") (pintype "passive"))
      (node (ref "J3") (pin "2") (pinfunction "2_2") (pintype "passive"))
    )
    (net (code "30") (name "SPARE5-MAG-SDA") (class "Default")
      (node (ref "CF1.2") (pin "1") (pinfunction "1_1") (pintype "passive"))
      (node (ref "CF1.2") (pin "2") (pinfunction "2_2") (pintype "passive"))
      (node (ref "CF2.2") (pin "1") (pinfunction "1_1") (pintype "passive"))
      (node (ref "CF2.2") (pin "2") (pinfunction "2_2") (pintype "passive"))
      (node (ref "CF3.2") (pin "1") (pinfunction "1_1") (pintype "passive"))
      (node (ref "CF3.2") (pin "2") (pinfunction "2_2") (pintype "passive"))
      (node (ref "CF4.2") (pin "1") (pinfunction "1_1") (pintype "passive"))
      (node (ref "CF4.2") (pin "2") (pinfunction "2_2") (pintype "passive"))
      (node (ref "CF5.2") (pin "1") (pinfunction "1_1") (pintype "passive"))
      (node (ref "CF5.2") (pin "2") (pinfunction "2_2") (pintype "passive"))
      (node (ref "CF6.2") (pin "1") (pinfunction "1_1") (pintype "passive"))
      (node (ref "CF6.2") (pin "2") (pinfunction "2_2") (pintype "passive"))
      (node (ref "CF7.2") (pin "1") (pinfunction "1_1") (pintype "passive"))
      (node (ref "CF7.2") (pin "2") (pinfunction "2_2") (pintype "passive"))
      (node (ref "CF8.2") (pin "1") (pinfunction "1_1") (pintype "passive"))
      (node (ref "CF8.2") (pin "2") (pinfunction "2_2") (pintype "passive"))
      (node (ref "J1") (pin "19") (pinfunction "19_19") (pintype "passive"))
      (node (ref "J1") (pin "20") (pinfunction "20_20") (pintype "passive"))
      (node (ref "J3") (pin "1") (pinfunction "1_1") (pintype "passive"))
    )
    (net (code "31") (name "UHF-TURNSTILE") (class "Default")
      (node (ref "CM1.3") (pin "RF-DOWN") (pinfunction "RF_RF-DOWN") (pintype "passive"))
      (node (ref "CM2.3") (pin "RF-DOWN") (pinfunction "RF_RF-DOWN") (pintype "passive"))
    )
    (net (code "32") (name "VBUS") (class "Default")
      (node (ref "CF1.2") (pin "21") (pinfunction "21_21") (pintype "passive"))
      (node (ref "CF1.2") (pin "22") (pinfunction "22_22") (pintype "passive"))
      (node (ref "CF1.2") (pin "23") (pinfunction "23_23") (pintype "passive"))
      (node (ref "CF1.2") (pin "24") (pinfunction "24_24") (pintype "passive"))
      (node (ref "CF1.2") (pin "25") (pinfunction "25_25") (pintype "passive"))
      (node (ref "CF1.2") (pin "26") (pinfunction "26_26") (pintype "passive"))
      (node (ref "CF2.2") (pin "21") (pinfunction "21_21") (pintype "passive"))
      (node (ref "CF2.2") (pin "22") (pinfunction "22_22") (pintype "passive"))
      (node (ref "CF2.2") (pin "23") (pinfunction "23_23") (pintype "passive"))
      (node (ref "CF2.2") (pin "24") (pinfunction "24_24") (pintype "passive"))
      (node (ref "CF2.2") (pin "25") (pinfunction "25_25") (pintype "passive"))
      (node (ref "CF2.2") (pin "26") (pinfunction "26_26") (pintype "passive"))
      (node (ref "CF3.2") (pin "21") (pinfunction "21_21") (pintype "passive"))
      (node (ref "CF3.2") (pin "22") (pinfunction "22_22") (pintype "passive"))
      (node (ref "CF3.2") (pin "23") (pinfunction "23_23") (pintype "passive"))
      (node (ref "CF3.2") (pin "24") (pinfunction "24_24") (pintype "passive"))
      (node (ref "CF3.2") (pin "25") (pinfunction "25_25") (pintype "passive"))
      (node (ref "CF3.2") (pin "26") (pinfunction "26_26") (pintype "passive"))
      (node (ref "CF4.2") (pin "21") (pinfunction "21_21") (pintype "passive"))
      (node (ref "CF4.2") (pin "22") (pinfunction "22_22") (pintype "passive"))
      (node (ref "CF4.2") (pin "23") (pinfunction "23_23") (pintype "passive"))
      (node (ref "CF4.2") (pin "24") (pinfunction "24_24") (pintype "passive"))
      (node (ref "CF4.2") (pin "25") (pinfunction "25_25") (pintype "passive"))
      (node (ref "CF4.2") (pin "26") (pinfunction "26_26") (pintype "passive"))
      (node (ref "CF5.2") (pin "21") (pinfunction "21_21") (pintype "passive"))
      (node (ref "CF5.2") (pin "22") (pinfunction "22_22") (pintype "passive"))
      (node (ref "CF5.2") (pin "23") (pinfunction "23_23") (pintype "passive"))
      (node (ref "CF5.2") (pin "24") (pinfunction "24_24") (pintype "passive"))
      (node (ref "CF5.2") (pin "25") (pinfunction "25_25") (pintype "passive"))
      (node (ref "CF5.2") (pin "26") (pinfunction "26_26") (pintype "passive"))
      (node (ref "CF6.2") (pin "21") (pinfunction "21_21") (pintype "passive"))
      (node (ref "CF6.2") (pin "22") (pinfunction "22_22") (pintype "passive"))
      (node (ref "CF6.2") (pin "23") (pinfunction "23_23") (pintype "passive"))
      (node (ref "CF6.2") (pin "24") (pinfunction "24_24") (pintype "passive"))
      (node (ref "CF6.2") (pin "25") (pinfunction "25_25") (pintype "passive"))
      (node (ref "CF6.2") (pin "26") (pinfunction "26_26") (pintype "passive"))
      (node (ref "CF7.2") (pin "21") (pinfunction "21_21") (pintype "passive"))
      (node (ref "CF7.2") (pin "22") (pinfunction "22_22") (pintype "passive"))
      (node (ref "CF7.2") (pin "23") (pinfunction "23_23") (pintype "passive"))
      (node (ref "CF7.2") (pin "24") (pinfunction "24_24") (pintype "passive"))
      (node (ref "CF7.2") (pin "25") (pinfunction "25_25") (pintype "passive"))
      (node (ref "CF7.2") (pin "26") (pinfunction "26_26") (pintype "passive"))
      (node (ref "CF8.2") (pin "21") (pinfunction "21_21") (pintype "passive"))
      (node (ref "CF8.2") (pin "22") (pinfunction "22_22") (pintype "passive"))
      (node (ref "CF8.2") (pin "23") (pinfunction "23_23") (pintype "passive"))
      (node (ref "CF8.2") (pin "24") (pinfunction "24_24") (pintype "passive"))
      (node (ref "CF8.2") (pin "25") (pinfunction "25_25") (pintype "passive"))
      (node (ref "CF8.2") (pin "26") (pinfunction "26_26") (pintype "passive"))
      (node (ref "J3") (pin "11") (pinfunction "11_11") (pintype "passive"))
      (node (ref "J3") (pin "12") (pinfunction "12_12") (pintype "passive"))
      (node (ref "J3") (pin "13") (pinfunction "13_13") (pintype "passive"))
    )
    (net (code "33") (name "unconnected-(FIDUCIAL1-PadFIDUCIAL)") (class "Default")
      (node (ref "FIDUCIAL1") (pin "FIDUCIAL") (pinfunction "FIDUCIAL_FIDUCIAL") (pintype "no_connect"))
    )
    (net (code "34") (name "unconnected-(FIDUCIAL2-PadFIDUCIAL)") (class "Default")
      (node (ref "FIDUCIAL2") (pin "FIDUCIAL") (pinfunction "FIDUCIAL_FIDUCIAL") (pintype "no_connect"))
    )
    (net (code "35") (name "unconnected-(FIDUCIAL3-PadFIDUCIAL)") (class "Default")
      (node (ref "FIDUCIAL3") (pin "FIDUCIAL") (pinfunction "FIDUCIAL_FIDUCIAL") (pintype "no_connect"))
    )
    (net (code "36") (name "~{SD}") (class "Default")
      (node (ref "CF1.2") (pin "39") (pinfunction "39_39") (pintype "passive"))
      (node (ref "CF1.2") (pin "40") (pinfunction "40_40") (pintype "passive"))
      (node (ref "CF2.2") (pin "39") (pinfunction "39_39") (pintype "passive"))
      (node (ref "CF2.2") (pin "40") (pinfunction "40_40") (pintype "passive"))
      (node (ref "CF3.2") (pin "39") (pinfunction "39_39") (pintype "passive"))
      (node (ref "CF3.2") (pin "40") (pinfunction "40_40") (pintype "passive"))
      (node (ref "CF4.2") (pin "39") (pinfunction "39_39") (pintype "passive"))
      (node (ref "CF4.2") (pin "40") (pinfunction "40_40") (pintype "passive"))
      (node (ref "CF5.2") (pin "39") (pinfunction "39_39") (pintype "passive"))
      (node (ref "CF5.2") (pin "40") (pinfunction "40_40") (pintype "passive"))
      (node (ref "CF6.2") (pin "39") (pinfunction "39_39") (pintype "passive"))
      (node (ref "CF6.2") (pin "40") (pinfunction "40_40") (pintype "passive"))
      (node (ref "CF7.2") (pin "39") (pinfunction "39_39") (pintype "passive"))
      (node (ref "CF7.2") (pin "40") (pinfunction "40_40") (pintype "passive"))
      (node (ref "CF8.2") (pin "39") (pinfunction "39_39") (pintype "passive"))
      (node (ref "CF8.2") (pin "40") (pinfunction "40_40") (pintype "passive"))
      (node (ref "J3") (pin "20") (pinfunction "20_20") (pintype "passive"))
    )
  )
)
